# DisplayStick.net
KiCad netlist of a schematic drawn in EAGLE
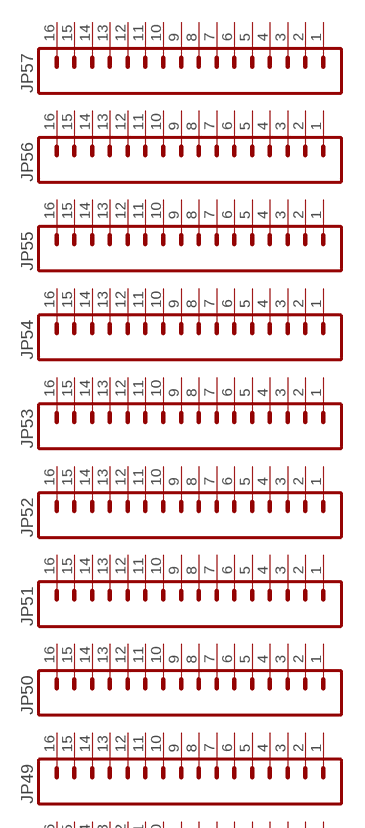
[diagram p0: schematic, sheet 1, part 1 of 2]
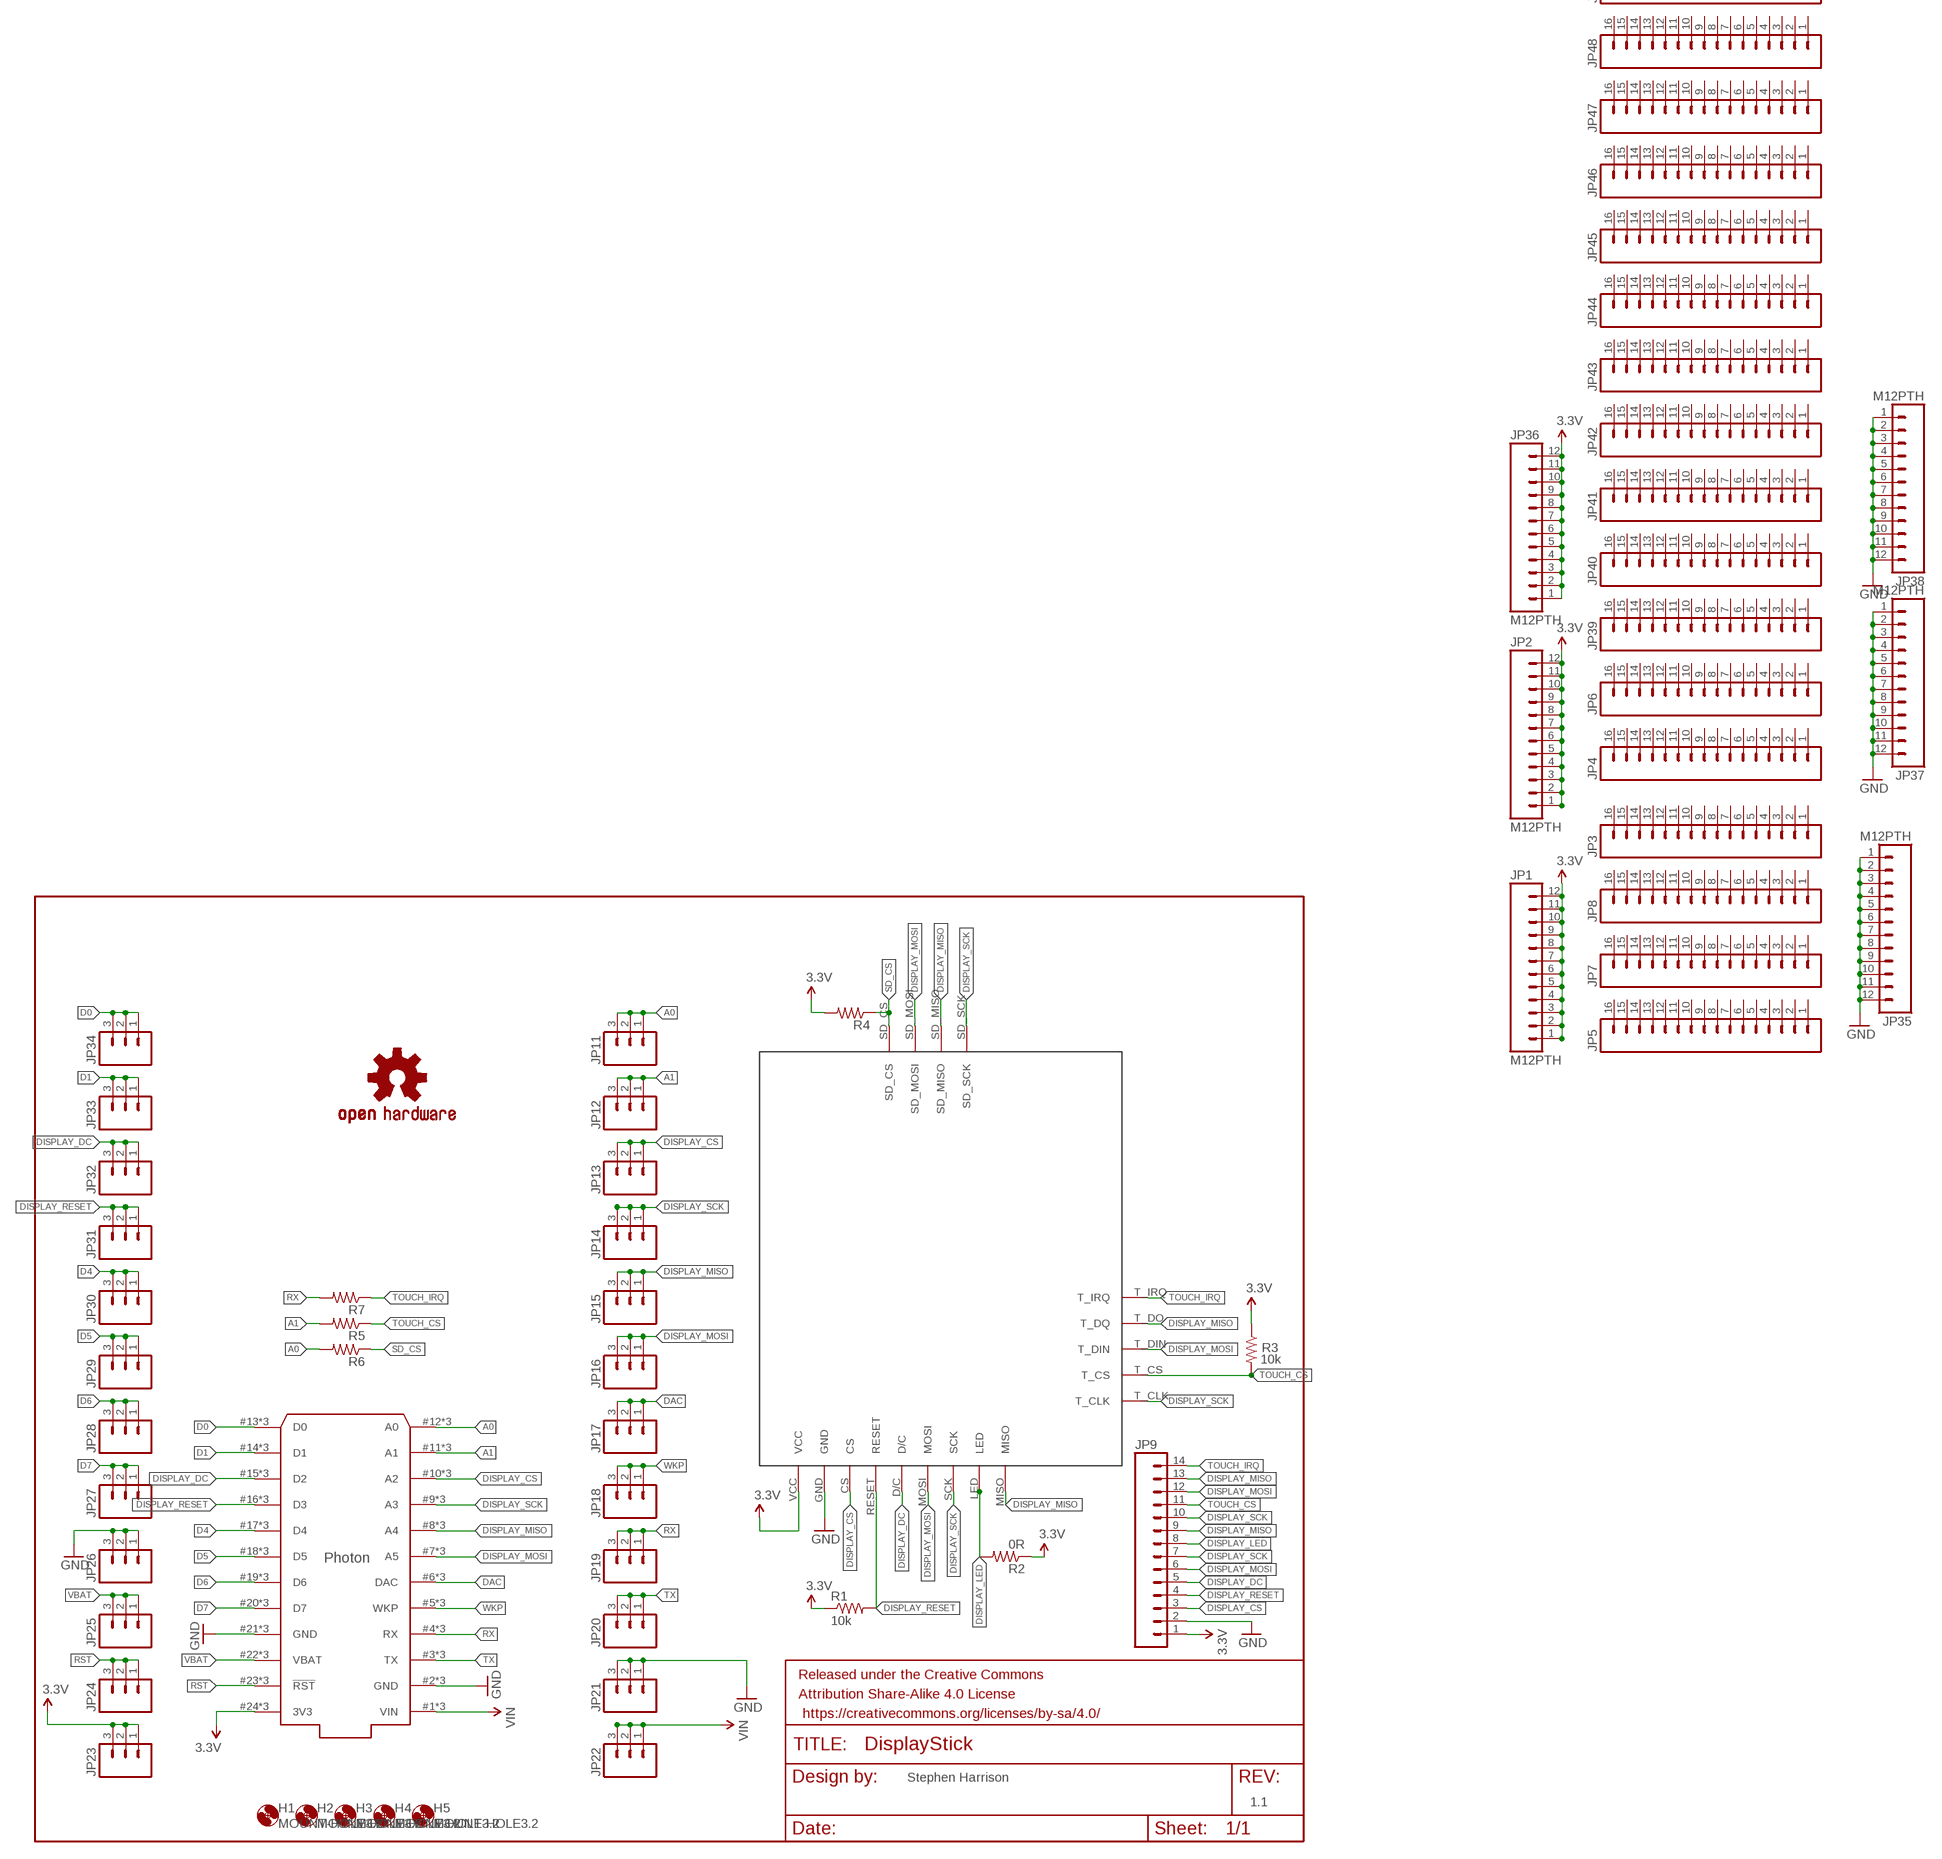
[diagram p1: schematic, sheet 1, part 2 of 2]

(export (version "E")
  (design (tool "Eeschema 10.0.6"))
  (components
    (comp (ref "FRAME1")
      (value "FRAME-LETTER")
      (footprint "eagle-import:CREATIVE_COMMONS")
      (libsource (lib "eagle-import") (part "FRAME-LETTER"))
    )
    (comp (ref "H1")
      (value "MOUNT-HOLE3.2")
      (footprint "eagle-import:3,2")
      (libsource (lib "eagle-import") (part "MOUNT-HOLE3.2"))
    )
    (comp (ref "H2")
      (value "MOUNT-HOLE3.2")
      (footprint "eagle-import:3,2")
      (libsource (lib "eagle-import") (part "MOUNT-HOLE3.2"))
    )
    (comp (ref "H3")
      (value "MOUNT-HOLE3.2")
      (footprint "eagle-import:3,2")
      (libsource (lib "eagle-import") (part "MOUNT-HOLE3.2"))
    )
    (comp (ref "H4")
      (value "MOUNT-HOLE3.2")
      (footprint "eagle-import:3,2")
      (libsource (lib "eagle-import") (part "MOUNT-HOLE3.2"))
    )
    (comp (ref "H5")
      (value "MOUNT-HOLE3.2")
      (footprint "eagle-import:3,2")
      (libsource (lib "eagle-import") (part "MOUNT-HOLE3.2"))
    )
    (comp (ref "JP1")
      (value "M12PTH")
      (footprint "eagle-import:1X12-SMALL-PADS")
      (libsource (lib "eagle-import") (part "M12PTH"))
    )
    (comp (ref "JP2")
      (value "M12PTH")
      (footprint "eagle-import:1X12-SMALL-PADS")
      (libsource (lib "eagle-import") (part "M12PTH"))
    )
    (comp (ref "JP3")
      (value "M161X16_NO_SILK")
      (footprint "eagle-import:1X16_NO_SILK")
      (libsource (lib "eagle-import") (part "M161X16_NO_SILK"))
    )
    (comp (ref "JP4")
      (value "M161X16_NO_SILK")
      (footprint "eagle-import:1X16_NO_SILK")
      (libsource (lib "eagle-import") (part "M161X16_NO_SILK"))
    )
    (comp (ref "JP5")
      (value "M161X16_NO_SILK")
      (footprint "eagle-import:1X16_NO_SILK")
      (libsource (lib "eagle-import") (part "M161X16_NO_SILK"))
    )
    (comp (ref "JP6")
      (value "M161X16_NO_SILK")
      (footprint "eagle-import:1X16_NO_SILK")
      (libsource (lib "eagle-import") (part "M161X16_NO_SILK"))
    )
    (comp (ref "JP7")
      (value "M161X16_NO_SILK")
      (footprint "eagle-import:1X16_NO_SILK")
      (libsource (lib "eagle-import") (part "M161X16_NO_SILK"))
    )
    (comp (ref "JP8")
      (value "M161X16_NO_SILK")
      (footprint "eagle-import:1X16_NO_SILK")
      (libsource (lib "eagle-import") (part "M161X16_NO_SILK"))
    )
    (comp (ref "JP9")
      (value "M14")
      (footprint "eagle-import:1X14")
      (libsource (lib "eagle-import") (part "M14"))
    )
    (comp (ref "JP11")
      (value "M03PTH")
      (footprint "eagle-import:1X03")
      (libsource (lib "eagle-import") (part "M03PTH"))
    )
    (comp (ref "JP12")
      (value "M03PTH")
      (footprint "eagle-import:1X03")
      (libsource (lib "eagle-import") (part "M03PTH"))
    )
    (comp (ref "JP13")
      (value "M03PTH")
      (footprint "eagle-import:1X03")
      (libsource (lib "eagle-import") (part "M03PTH"))
    )
    (comp (ref "JP14")
      (value "M03PTH")
      (footprint "eagle-import:1X03")
      (libsource (lib "eagle-import") (part "M03PTH"))
    )
    (comp (ref "JP15")
      (value "M03PTH")
      (footprint "eagle-import:1X03")
      (libsource (lib "eagle-import") (part "M03PTH"))
    )
    (comp (ref "JP16")
      (value "M03PTH")
      (footprint "eagle-import:1X03")
      (libsource (lib "eagle-import") (part "M03PTH"))
    )
    (comp (ref "JP17")
      (value "M03PTH")
      (footprint "eagle-import:1X03")
      (libsource (lib "eagle-import") (part "M03PTH"))
    )
    (comp (ref "JP18")
      (value "M03PTH")
      (footprint "eagle-import:1X03")
      (libsource (lib "eagle-import") (part "M03PTH"))
    )
    (comp (ref "JP19")
      (value "M03PTH")
      (footprint "eagle-import:1X03")
      (libsource (lib "eagle-import") (part "M03PTH"))
    )
    (comp (ref "JP20")
      (value "M03PTH")
      (footprint "eagle-import:1X03")
      (libsource (lib "eagle-import") (part "M03PTH"))
    )
    (comp (ref "JP21")
      (value "M03PTH")
      (footprint "eagle-import:1X03")
      (libsource (lib "eagle-import") (part "M03PTH"))
    )
    (comp (ref "JP22")
      (value "M03PTH")
      (footprint "eagle-import:1X03")
      (libsource (lib "eagle-import") (part "M03PTH"))
    )
    (comp (ref "JP23")
      (value "M03PTH")
      (footprint "eagle-import:1X03")
      (libsource (lib "eagle-import") (part "M03PTH"))
    )
    (comp (ref "JP24")
      (value "M03PTH")
      (footprint "eagle-import:1X03")
      (libsource (lib "eagle-import") (part "M03PTH"))
    )
    (comp (ref "JP25")
      (value "M03PTH")
      (footprint "eagle-import:1X03")
      (libsource (lib "eagle-import") (part "M03PTH"))
    )
    (comp (ref "JP26")
      (value "M03PTH")
      (footprint "eagle-import:1X03")
      (libsource (lib "eagle-import") (part "M03PTH"))
    )
    (comp (ref "JP27")
      (value "M03PTH")
      (footprint "eagle-import:1X03")
      (libsource (lib "eagle-import") (part "M03PTH"))
    )
    (comp (ref "JP28")
      (value "M03PTH")
      (footprint "eagle-import:1X03")
      (libsource (lib "eagle-import") (part "M03PTH"))
    )
    (comp (ref "JP29")
      (value "M03PTH")
      (footprint "eagle-import:1X03")
      (libsource (lib "eagle-import") (part "M03PTH"))
    )
    (comp (ref "JP30")
      (value "M03PTH")
      (footprint "eagle-import:1X03")
      (libsource (lib "eagle-import") (part "M03PTH"))
    )
    (comp (ref "JP31")
      (value "M03PTH")
      (footprint "eagle-import:1X03")
      (libsource (lib "eagle-import") (part "M03PTH"))
    )
    (comp (ref "JP32")
      (value "M03PTH")
      (footprint "eagle-import:1X03")
      (libsource (lib "eagle-import") (part "M03PTH"))
    )
    (comp (ref "JP33")
      (value "M03PTH")
      (footprint "eagle-import:1X03")
      (libsource (lib "eagle-import") (part "M03PTH"))
    )
    (comp (ref "JP34")
      (value "M03PTH")
      (footprint "eagle-import:1X03")
      (libsource (lib "eagle-import") (part "M03PTH"))
    )
    (comp (ref "JP35")
      (value "M12PTH")
      (footprint "eagle-import:1X12-SMALL-PADS")
      (libsource (lib "eagle-import") (part "M12PTH"))
    )
    (comp (ref "JP36")
      (value "M12PTH")
      (footprint "eagle-import:1X12-SMALL-PADS")
      (libsource (lib "eagle-import") (part "M12PTH"))
    )
    (comp (ref "JP37")
      (value "M12PTH")
      (footprint "eagle-import:1X12-SMALL-PADS")
      (libsource (lib "eagle-import") (part "M12PTH"))
    )
    (comp (ref "JP38")
      (value "M12PTH")
      (footprint "eagle-import:1X12-SMALL-PADS")
      (libsource (lib "eagle-import") (part "M12PTH"))
    )
    (comp (ref "JP39")
      (value "M161X16_NO_SILK")
      (footprint "eagle-import:1X16_NO_SILK")
      (libsource (lib "eagle-import") (part "M161X16_NO_SILK"))
    )
    (comp (ref "JP40")
      (value "M161X16_NO_SILK")
      (footprint "eagle-import:1X16_NO_SILK")
      (libsource (lib "eagle-import") (part "M161X16_NO_SILK"))
    )
    (comp (ref "JP41")
      (value "M161X16_NO_SILK")
      (footprint "eagle-import:1X16_NO_SILK")
      (libsource (lib "eagle-import") (part "M161X16_NO_SILK"))
    )
    (comp (ref "JP42")
      (value "M161X16_NO_SILK")
      (footprint "eagle-import:1X16_NO_SILK")
      (libsource (lib "eagle-import") (part "M161X16_NO_SILK"))
    )
    (comp (ref "JP43")
      (value "M161X16_NO_SILK")
      (footprint "eagle-import:1X16_NO_SILK")
      (libsource (lib "eagle-import") (part "M161X16_NO_SILK"))
    )
    (comp (ref "JP44")
      (value "M161X16_NO_SILK")
      (footprint "eagle-import:1X16_NO_SILK")
      (libsource (lib "eagle-import") (part "M161X16_NO_SILK"))
    )
    (comp (ref "JP45")
      (value "M161X16_NO_SILK")
      (footprint "eagle-import:1X16_NO_SILK")
      (libsource (lib "eagle-import") (part "M161X16_NO_SILK"))
    )
    (comp (ref "JP46")
      (value "M161X16_NO_SILK")
      (footprint "eagle-import:1X16_NO_SILK")
      (libsource (lib "eagle-import") (part "M161X16_NO_SILK"))
    )
    (comp (ref "JP47")
      (value "M161X16_NO_SILK")
      (footprint "eagle-import:1X16_NO_SILK")
      (libsource (lib "eagle-import") (part "M161X16_NO_SILK"))
    )
    (comp (ref "JP48")
      (value "M161X16_NO_SILK")
      (footprint "eagle-import:1X16_NO_SILK")
      (libsource (lib "eagle-import") (part "M161X16_NO_SILK"))
    )
    (comp (ref "JP49")
      (value "M161X16_NO_SILK")
      (footprint "eagle-import:1X16_NO_SILK")
      (libsource (lib "eagle-import") (part "M161X16_NO_SILK"))
    )
    (comp (ref "JP50")
      (value "M161X16_NO_SILK")
      (footprint "eagle-import:1X16_NO_SILK")
      (libsource (lib "eagle-import") (part "M161X16_NO_SILK"))
    )
    (comp (ref "JP51")
      (value "M161X16_NO_SILK")
      (footprint "eagle-import:1X16_NO_SILK")
      (libsource (lib "eagle-import") (part "M161X16_NO_SILK"))
    )
    (comp (ref "JP52")
      (value "M161X16_NO_SILK")
      (footprint "eagle-import:1X16_NO_SILK")
      (libsource (lib "eagle-import") (part "M161X16_NO_SILK"))
    )
    (comp (ref "JP53")
      (value "M161X16_NO_SILK")
      (footprint "eagle-import:1X16_NO_SILK")
      (libsource (lib "eagle-import") (part "M161X16_NO_SILK"))
    )
    (comp (ref "JP54")
      (value "M161X16_NO_SILK")
      (footprint "eagle-import:1X16_NO_SILK")
      (libsource (lib "eagle-import") (part "M161X16_NO_SILK"))
    )
    (comp (ref "JP55")
      (value "M161X16_NO_SILK")
      (footprint "eagle-import:1X16_NO_SILK")
      (libsource (lib "eagle-import") (part "M161X16_NO_SILK"))
    )
    (comp (ref "JP56")
      (value "M161X16_NO_SILK")
      (footprint "eagle-import:1X16_NO_SILK")
      (libsource (lib "eagle-import") (part "M161X16_NO_SILK"))
    )
    (comp (ref "JP57")
      (value "M161X16_NO_SILK")
      (footprint "eagle-import:1X16_NO_SILK")
      (libsource (lib "eagle-import") (part "M161X16_NO_SILK"))
    )
    (comp (ref "LOGO1")
      (value "OSHW-LOGOL")
      (footprint "eagle-import:OSHW-LOGO-L")
      (libsource (lib "eagle-import") (part "OSHW-LOGOL"))
    )
    (comp (ref "R1")
      (value "10k")
      (footprint "eagle-import:1206")
      (libsource (lib "eagle-import") (part "RESISTOR1206"))
    )
    (comp (ref "R2")
      (value "0R")
      (footprint "eagle-import:1206")
      (libsource (lib "eagle-import") (part "RESISTOR1206"))
    )
    (comp (ref "R3")
      (value "10k")
      (footprint "eagle-import:1206")
      (libsource (lib "eagle-import") (part "RESISTOR1206"))
    )
    (comp (ref "R4")
      (value "RESISTOR1206")
      (footprint "eagle-import:1206")
      (libsource (lib "eagle-import") (part "RESISTOR1206"))
    )
    (comp (ref "R5")
      (value "RESISTOR1206")
      (footprint "eagle-import:1206")
      (libsource (lib "eagle-import") (part "RESISTOR1206"))
    )
    (comp (ref "R6")
      (value "RESISTOR1206")
      (footprint "eagle-import:1206")
      (libsource (lib "eagle-import") (part "RESISTOR1206"))
    )
    (comp (ref "R7")
      (value "RESISTOR1206")
      (footprint "eagle-import:1206")
      (libsource (lib "eagle-import") (part "RESISTOR1206"))
    )
    (comp (ref "U$1")
      (value "TJCTM240")
      (footprint "eagle-import:TJCTM240")
      (libsource (lib "eagle-import") (part "TJCTM240"))
    )
    (comp (ref "U$3")
      (value "PHOTON_WITH_STACKABLE_HEADERS")
      (footprint "eagle-import:PHOTON_STACKABLE")
      (libsource (lib "eagle-import") (part "PHOTON_WITH_STACKABLE_HEADERS"))
    )
  )
  (nets
    (net (code "1") (name "3.3V") (class "Default")
      (node (ref "JP1") (pin "1") (pinfunction "1_1") (pintype "passive"))
      (node (ref "JP1") (pin "10") (pinfunction "10_10") (pintype "passive"))
      (node (ref "JP1") (pin "11") (pinfunction "11_11") (pintype "passive"))
      (node (ref "JP1") (pin "12") (pinfunction "12_12") (pintype "passive"))
      (node (ref "JP1") (pin "2") (pinfunction "2_2") (pintype "passive"))
      (node (ref "JP1") (pin "3") (pinfunction "3_3") (pintype "passive"))
      (node (ref "JP1") (pin "4") (pinfunction "4_4") (pintype "passive"))
      (node (ref "JP1") (pin "5") (pinfunction "5_5") (pintype "passive"))
      (node (ref "JP1") (pin "6") (pinfunction "6_6") (pintype "passive"))
      (node (ref "JP1") (pin "7") (pinfunction "7_7") (pintype "passive"))
      (node (ref "JP1") (pin "8") (pinfunction "8_8") (pintype "passive"))
      (node (ref "JP1") (pin "9") (pinfunction "9_9") (pintype "passive"))
      (node (ref "JP2") (pin "1") (pinfunction "1_1") (pintype "passive"))
      (node (ref "JP2") (pin "10") (pinfunction "10_10") (pintype "passive"))
      (node (ref "JP2") (pin "11") (pinfunction "11_11") (pintype "passive"))
      (node (ref "JP2") (pin "12") (pinfunction "12_12") (pintype "passive"))
      (node (ref "JP2") (pin "2") (pinfunction "2_2") (pintype "passive"))
      (node (ref "JP2") (pin "3") (pinfunction "3_3") (pintype "passive"))
      (node (ref "JP2") (pin "4") (pinfunction "4_4") (pintype "passive"))
      (node (ref "JP2") (pin "5") (pinfunction "5_5") (pintype "passive"))
      (node (ref "JP2") (pin "6") (pinfunction "6_6") (pintype "passive"))
      (node (ref "JP2") (pin "7") (pinfunction "7_7") (pintype "passive"))
      (node (ref "JP2") (pin "8") (pinfunction "8_8") (pintype "passive"))
      (node (ref "JP2") (pin "9") (pinfunction "9_9") (pintype "passive"))
      (node (ref "JP23") (pin "1") (pinfunction "1_1") (pintype "passive"))
      (node (ref "JP23") (pin "2") (pinfunction "2_2") (pintype "passive"))
      (node (ref "JP23") (pin "3") (pinfunction "3_3") (pintype "passive"))
      (node (ref "JP36") (pin "1") (pinfunction "1_1") (pintype "passive"))
      (node (ref "JP36") (pin "10") (pinfunction "10_10") (pintype "passive"))
      (node (ref "JP36") (pin "11") (pinfunction "11_11") (pintype "passive"))
      (node (ref "JP36") (pin "12") (pinfunction "12_12") (pintype "passive"))
      (node (ref "JP36") (pin "2") (pinfunction "2_2") (pintype "passive"))
      (node (ref "JP36") (pin "3") (pinfunction "3_3") (pintype "passive"))
      (node (ref "JP36") (pin "4") (pinfunction "4_4") (pintype "passive"))
      (node (ref "JP36") (pin "5") (pinfunction "5_5") (pintype "passive"))
      (node (ref "JP36") (pin "6") (pinfunction "6_6") (pintype "passive"))
      (node (ref "JP36") (pin "7") (pinfunction "7_7") (pintype "passive"))
      (node (ref "JP36") (pin "8") (pinfunction "8_8") (pintype "passive"))
      (node (ref "JP36") (pin "9") (pinfunction "9_9") (pintype "passive"))
      (node (ref "JP9") (pin "1") (pinfunction "1_1") (pintype "passive"))
      (node (ref "R1") (pin "1") (pinfunction "1_1") (pintype "passive"))
      (node (ref "R2") (pin "1") (pinfunction "1_1") (pintype "passive"))
      (node (ref "R3") (pin "1") (pinfunction "1_1") (pintype "passive"))
      (node (ref "R4") (pin "2") (pinfunction "2_2") (pintype "passive"))
      (node (ref "U$1") (pin "VCC") (pinfunction "VCC_VCC") (pintype "bidirectional"))
      (node (ref "U$3") (pin "#24") (pinfunction "3V3_#24") (pintype "power_in"))
      (node (ref "U$3") (pin "24") (pinfunction "3V3_24") (pintype "power_in"))
      (node (ref "U$3") (pin "@24") (pinfunction "3V3_@24") (pintype "power_in"))
    )
    (net (code "2") (name "A0") (class "Default")
      (node (ref "JP11") (pin "1") (pinfunction "1_1") (pintype "passive"))
      (node (ref "JP11") (pin "2") (pinfunction "2_2") (pintype "passive"))
      (node (ref "JP11") (pin "3") (pinfunction "3_3") (pintype "passive"))
      (node (ref "R6") (pin "2") (pinfunction "2_2") (pintype "passive"))
      (node (ref "U$3") (pin "#12") (pinfunction "A0_#12") (pintype "bidirectional"))
      (node (ref "U$3") (pin "12") (pinfunction "A0_12") (pintype "bidirectional"))
      (node (ref "U$3") (pin "@12") (pinfunction "A0_@12") (pintype "bidirectional"))
    )
    (net (code "3") (name "A1") (class "Default")
      (node (ref "JP12") (pin "1") (pinfunction "1_1") (pintype "passive"))
      (node (ref "JP12") (pin "2") (pinfunction "2_2") (pintype "passive"))
      (node (ref "JP12") (pin "3") (pinfunction "3_3") (pintype "passive"))
      (node (ref "R5") (pin "2") (pinfunction "2_2") (pintype "passive"))
      (node (ref "U$3") (pin "#11") (pinfunction "A1_#11") (pintype "bidirectional"))
      (node (ref "U$3") (pin "11") (pinfunction "A1_11") (pintype "bidirectional"))
      (node (ref "U$3") (pin "@11") (pinfunction "A1_@11") (pintype "bidirectional"))
    )
    (net (code "4") (name "D0") (class "Default")
      (node (ref "JP34") (pin "1") (pinfunction "1_1") (pintype "passive"))
      (node (ref "JP34") (pin "2") (pinfunction "2_2") (pintype "passive"))
      (node (ref "JP34") (pin "3") (pinfunction "3_3") (pintype "passive"))
      (node (ref "U$3") (pin "#13") (pinfunction "D0_#13") (pintype "bidirectional"))
      (node (ref "U$3") (pin "13") (pinfunction "D0_13") (pintype "bidirectional"))
      (node (ref "U$3") (pin "@13") (pinfunction "D0_@13") (pintype "bidirectional"))
    )
    (net (code "5") (name "D1") (class "Default")
      (node (ref "JP33") (pin "1") (pinfunction "1_1") (pintype "passive"))
      (node (ref "JP33") (pin "2") (pinfunction "2_2") (pintype "passive"))
      (node (ref "JP33") (pin "3") (pinfunction "3_3") (pintype "passive"))
      (node (ref "U$3") (pin "#14") (pinfunction "D1_#14") (pintype "bidirectional"))
      (node (ref "U$3") (pin "14") (pinfunction "D1_14") (pintype "bidirectional"))
      (node (ref "U$3") (pin "@14") (pinfunction "D1_@14") (pintype "bidirectional"))
    )
    (net (code "6") (name "D4") (class "Default")
      (node (ref "JP30") (pin "1") (pinfunction "1_1") (pintype "passive"))
      (node (ref "JP30") (pin "2") (pinfunction "2_2") (pintype "passive"))
      (node (ref "JP30") (pin "3") (pinfunction "3_3") (pintype "passive"))
      (node (ref "U$3") (pin "#17") (pinfunction "D4_#17") (pintype "bidirectional"))
      (node (ref "U$3") (pin "17") (pinfunction "D4_17") (pintype "bidirectional"))
      (node (ref "U$3") (pin "@17") (pinfunction "D4_@17") (pintype "bidirectional"))
    )
    (net (code "7") (name "D5") (class "Default")
      (node (ref "JP29") (pin "1") (pinfunction "1_1") (pintype "passive"))
      (node (ref "JP29") (pin "2") (pinfunction "2_2") (pintype "passive"))
      (node (ref "JP29") (pin "3") (pinfunction "3_3") (pintype "passive"))
      (node (ref "U$3") (pin "#18") (pinfunction "D5_#18") (pintype "bidirectional"))
      (node (ref "U$3") (pin "18") (pinfunction "D5_18") (pintype "bidirectional"))
      (node (ref "U$3") (pin "@18") (pinfunction "D5_@18") (pintype "bidirectional"))
    )
    (net (code "8") (name "D6") (class "Default")
      (node (ref "JP28") (pin "1") (pinfunction "1_1") (pintype "passive"))
      (node (ref "JP28") (pin "2") (pinfunction "2_2") (pintype "passive"))
      (node (ref "JP28") (pin "3") (pinfunction "3_3") (pintype "passive"))
      (node (ref "U$3") (pin "#19") (pinfunction "D6_#19") (pintype "bidirectional"))
      (node (ref "U$3") (pin "19") (pinfunction "D6_19") (pintype "bidirectional"))
      (node (ref "U$3") (pin "@19") (pinfunction "D6_@19") (pintype "bidirectional"))
    )
    (net (code "9") (name "D7") (class "Default")
      (node (ref "JP27") (pin "1") (pinfunction "1_1") (pintype "passive"))
      (node (ref "JP27") (pin "2") (pinfunction "2_2") (pintype "passive"))
      (node (ref "JP27") (pin "3") (pinfunction "3_3") (pintype "passive"))
      (node (ref "U$3") (pin "#20") (pinfunction "D7_#20") (pintype "bidirectional"))
      (node (ref "U$3") (pin "20") (pinfunction "D7_20") (pintype "bidirectional"))
      (node (ref "U$3") (pin "@20") (pinfunction "D7_@20") (pintype "bidirectional"))
    )
    (net (code "10") (name "DAC") (class "Default")
      (node (ref "JP17") (pin "1") (pinfunction "1_1") (pintype "passive"))
      (node (ref "JP17") (pin "2") (pinfunction "2_2") (pintype "passive"))
      (node (ref "JP17") (pin "3") (pinfunction "3_3") (pintype "passive"))
      (node (ref "U$3") (pin "#6") (pinfunction "DAC_#6") (pintype "bidirectional"))
      (node (ref "U$3") (pin "6") (pinfunction "DAC_6") (pintype "bidirectional"))
      (node (ref "U$3") (pin "@6") (pinfunction "DAC_@6") (pintype "bidirectional"))
    )
    (net (code "11") (name "DISPLAY_CS") (class "Default")
      (node (ref "JP13") (pin "1") (pinfunction "1_1") (pintype "passive"))
      (node (ref "JP13") (pin "2") (pinfunction "2_2") (pintype "passive"))
      (node (ref "JP13") (pin "3") (pinfunction "3_3") (pintype "passive"))
      (node (ref "JP9") (pin "3") (pinfunction "3_3") (pintype "passive"))
      (node (ref "U$1") (pin "CS") (pinfunction "CS_CS") (pintype "bidirectional"))
      (node (ref "U$3") (pin "#10") (pinfunction "A2_#10") (pintype "bidirectional"))
      (node (ref "U$3") (pin "10") (pinfunction "A2_10") (pintype "bidirectional"))
      (node (ref "U$3") (pin "@10") (pinfunction "A2_@10") (pintype "bidirectional"))
    )
    (net (code "12") (name "DISPLAY_DC") (class "Default")
      (node (ref "JP32") (pin "1") (pinfunction "1_1") (pintype "passive"))
      (node (ref "JP32") (pin "2") (pinfunction "2_2") (pintype "passive"))
      (node (ref "JP32") (pin "3") (pinfunction "3_3") (pintype "passive"))
      (node (ref "JP9") (pin "5") (pinfunction "5_5") (pintype "passive"))
      (node (ref "U$1") (pin "D/C") (pinfunction "D/C_D/C") (pintype "bidirectional"))
      (node (ref "U$3") (pin "#15") (pinfunction "D2_#15") (pintype "bidirectional"))
      (node (ref "U$3") (pin "15") (pinfunction "D2_15") (pintype "bidirectional"))
      (node (ref "U$3") (pin "@15") (pinfunction "D2_@15") (pintype "bidirectional"))
    )
    (net (code "13") (name "DISPLAY_LED") (class "Default")
      (node (ref "JP9") (pin "8") (pinfunction "8_8") (pintype "passive"))
      (node (ref "R2") (pin "2") (pinfunction "2_2") (pintype "passive"))
      (node (ref "U$1") (pin "LED") (pinfunction "LED_LED") (pintype "bidirectional"))
    )
    (net (code "14") (name "DISPLAY_MISO") (class "Default")
      (node (ref "JP15") (pin "1") (pinfunction "1_1") (pintype "passive"))
      (node (ref "JP15") (pin "2") (pinfunction "2_2") (pintype "passive"))
      (node (ref "JP15") (pin "3") (pinfunction "3_3") (pintype "passive"))
      (node (ref "JP9") (pin "13") (pinfunction "13_13") (pintype "passive"))
      (node (ref "JP9") (pin "9") (pinfunction "9_9") (pintype "passive"))
      (node (ref "U$1") (pin "MISO") (pinfunction "MISO_MISO") (pintype "bidirectional"))
      (node (ref "U$1") (pin "SD_MISO") (pinfunction "SD_MISO_SD_MISO") (pintype "bidirectional"))
      (node (ref "U$1") (pin "T_DO") (pinfunction "T_DQ_T_DO") (pintype "bidirectional"))
      (node (ref "U$3") (pin "#8") (pinfunction "A4_#8") (pintype "bidirectional"))
      (node (ref "U$3") (pin "8") (pinfunction "A4_8") (pintype "bidirectional"))
      (node (ref "U$3") (pin "@8") (pinfunction "A4_@8") (pintype "bidirectional"))
    )
    (net (code "15") (name "DISPLAY_MOSI") (class "Default")
      (node (ref "JP16") (pin "1") (pinfunction "1_1") (pintype "passive"))
      (node (ref "JP16") (pin "2") (pinfunction "2_2") (pintype "passive"))
      (node (ref "JP16") (pin "3") (pinfunction "3_3") (pintype "passive"))
      (node (ref "JP9") (pin "12") (pinfunction "12_12") (pintype "passive"))
      (node (ref "JP9") (pin "6") (pinfunction "6_6") (pintype "passive"))
      (node (ref "U$1") (pin "MOSI") (pinfunction "MOSI_MOSI") (pintype "bidirectional"))
      (node (ref "U$1") (pin "SD_MOSI") (pinfunction "SD_MOSI_SD_MOSI") (pintype "bidirectional"))
      (node (ref "U$1") (pin "T_DIN") (pinfunction "T_DIN_T_DIN") (pintype "bidirectional"))
      (node (ref "U$3") (pin "#7") (pinfunction "A5_#7") (pintype "bidirectional"))
      (node (ref "U$3") (pin "7") (pinfunction "A5_7") (pintype "bidirectional"))
      (node (ref "U$3") (pin "@7") (pinfunction "A5_@7") (pintype "bidirectional"))
    )
    (net (code "16") (name "DISPLAY_RESET") (class "Default")
      (node (ref "JP31") (pin "1") (pinfunction "1_1") (pintype "passive"))
      (node (ref "JP31") (pin "2") (pinfunction "2_2") (pintype "passive"))
      (node (ref "JP31") (pin "3") (pinfunction "3_3") (pintype "passive"))
      (node (ref "JP9") (pin "4") (pinfunction "4_4") (pintype "passive"))
      (node (ref "R1") (pin "2") (pinfunction "2_2") (pintype "passive"))
      (node (ref "U$1") (pin "RESET") (pinfunction "RESET_RESET") (pintype "bidirectional"))
      (node (ref "U$3") (pin "#16") (pinfunction "D3_#16") (pintype "bidirectional"))
      (node (ref "U$3") (pin "16") (pinfunction "D3_16") (pintype "bidirectional"))
      (node (ref "U$3") (pin "@16") (pinfunction "D3_@16") (pintype "bidirectional"))
    )
    (net (code "17") (name "DISPLAY_SCK") (class "Default")
      (node (ref "JP14") (pin "1") (pinfunction "1_1") (pintype "passive"))
      (node (ref "JP14") (pin "2") (pinfunction "2_2") (pintype "passive"))
      (node (ref "JP14") (pin "3") (pinfunction "3_3") (pintype "passive"))
      (node (ref "JP9") (pin "10") (pinfunction "10_10") (pintype "passive"))
      (node (ref "JP9") (pin "7") (pinfunction "7_7") (pintype "passive"))
      (node (ref "U$1") (pin "SCK") (pinfunction "SCK_SCK") (pintype "bidirectional"))
      (node (ref "U$1") (pin "SD_SCK") (pinfunction "SD_SCK_SD_SCK") (pintype "bidirectional"))
      (node (ref "U$1") (pin "T_CLK") (pinfunction "T_CLK_T_CLK") (pintype "bidirectional"))
      (node (ref "U$3") (pin "#9") (pinfunction "A3_#9") (pintype "bidirectional"))
      (node (ref "U$3") (pin "9") (pinfunction "A3_9") (pintype "bidirectional"))
      (node (ref "U$3") (pin "@9") (pinfunction "A3_@9") (pintype "bidirectional"))
    )
    (net (code "18") (name "GND") (class "Default")
      (node (ref "JP21") (pin "1") (pinfunction "1_1") (pintype "passive"))
      (node (ref "JP21") (pin "2") (pinfunction "2_2") (pintype "passive"))
      (node (ref "JP21") (pin "3") (pinfunction "3_3") (pintype "passive"))
      (node (ref "JP26") (pin "1") (pinfunction "1_1") (pintype "passive"))
      (node (ref "JP26") (pin "2") (pinfunction "2_2") (pintype "passive"))
      (node (ref "JP26") (pin "3") (pinfunction "3_3") (pintype "passive"))
      (node (ref "JP35") (pin "1") (pinfunction "1_1") (pintype "passive"))
      (node (ref "JP35") (pin "10") (pinfunction "10_10") (pintype "passive"))
      (node (ref "JP35") (pin "11") (pinfunction "11_11") (pintype "passive"))
      (node (ref "JP35") (pin "12") (pinfunction "12_12") (pintype "passive"))
      (node (ref "JP35") (pin "2") (pinfunction "2_2") (pintype "passive"))
      (node (ref "JP35") (pin "3") (pinfunction "3_3") (pintype "passive"))
      (node (ref "JP35") (pin "4") (pinfunction "4_4") (pintype "passive"))
      (node (ref "JP35") (pin "5") (pinfunction "5_5") (pintype "passive"))
      (node (ref "JP35") (pin "6") (pinfunction "6_6") (pintype "passive"))
      (node (ref "JP35") (pin "7") (pinfunction "7_7") (pintype "passive"))
      (node (ref "JP35") (pin "8") (pinfunction "8_8") (pintype "passive"))
      (node (ref "JP35") (pin "9") (pinfunction "9_9") (pintype "passive"))
      (node (ref "JP37") (pin "1") (pinfunction "1_1") (pintype "passive"))
      (node (ref "JP37") (pin "10") (pinfunction "10_10") (pintype "passive"))
      (node (ref "JP37") (pin "11") (pinfunction "11_11") (pintype "passive"))
      (node (ref "JP37") (pin "12") (pinfunction "12_12") (pintype "passive"))
      (node (ref "JP37") (pin "2") (pinfunction "2_2") (pintype "passive"))
      (node (ref "JP37") (pin "3") (pinfunction "3_3") (pintype "passive"))
      (node (ref "JP37") (pin "4") (pinfunction "4_4") (pintype "passive"))
      (node (ref "JP37") (pin "5") (pinfunction "5_5") (pintype "passive"))
      (node (ref "JP37") (pin "6") (pinfunction "6_6") (pintype "passive"))
      (node (ref "JP37") (pin "7") (pinfunction "7_7") (pintype "passive"))
      (node (ref "JP37") (pin "8") (pinfunction "8_8") (pintype "passive"))
      (node (ref "JP37") (pin "9") (pinfunction "9_9") (pintype "passive"))
      (node (ref "JP38") (pin "1") (pinfunction "1_1") (pintype "passive"))
      (node (ref "JP38") (pin "10") (pinfunction "10_10") (pintype "passive"))
      (node (ref "JP38") (pin "11") (pinfunction "11_11") (pintype "passive"))
      (node (ref "JP38") (pin "12") (pinfunction "12_12") (pintype "passive"))
      (node (ref "JP38") (pin "2") (pinfunction "2_2") (pintype "passive"))
      (node (ref "JP38") (pin "3") (pinfunction "3_3") (pintype "passive"))
      (node (ref "JP38") (pin "4") (pinfunction "4_4") (pintype "passive"))
      (node (ref "JP38") (pin "5") (pinfunction "5_5") (pintype "passive"))
      (node (ref "JP38") (pin "6") (pinfunction "6_6") (pintype "passive"))
      (node (ref "JP38") (pin "7") (pinfunction "7_7") (pintype "passive"))
      (node (ref "JP38") (pin "8") (pinfunction "8_8") (pintype "passive"))
      (node (ref "JP38") (pin "9") (pinfunction "9_9") (pintype "passive"))
      (node (ref "JP9") (pin "2") (pinfunction "2_2") (pintype "passive"))
      (node (ref "U$1") (pin "GND") (pinfunction "GND_GND") (pintype "bidirectional"))
      (node (ref "U$3") (pin "#2") (pinfunction "GND_#2") (pintype "power_in"))
      (node (ref "U$3") (pin "#21") (pinfunction "GND_#21") (pintype "power_in"))
      (node (ref "U$3") (pin "2") (pinfunction "GND_2") (pintype "power_in"))
      (node (ref "U$3") (pin "21") (pinfunction "GND_21") (pintype "power_in"))
      (node (ref "U$3") (pin "@2") (pinfunction "GND_@2") (pintype "power_in"))
      (node (ref "U$3") (pin "@21") (pinfunction "GND_@21") (pintype "power_in"))
    )
    (net (code "19") (name "RST") (class "Default")
      (node (ref "JP24") (pin "1") (pinfunction "1_1") (pintype "passive"))
      (node (ref "JP24") (pin "2") (pinfunction "2_2") (pintype "passive"))
      (node (ref "JP24") (pin "3") (pinfunction "3_3") (pintype "passive"))
      (node (ref "U$3") (pin "#23") (pinfunction "~{RST}_#23") (pintype "bidirectional"))
      (node (ref "U$3") (pin "23") (pinfunction "~{RST}_23") (pintype "bidirectional"))
      (node (ref "U$3") (pin "@23") (pinfunction "~{RST}_@23") (pintype "bidirectional"))
    )
    (net (code "20") (name "RX") (class "Default")
      (node (ref "JP19") (pin "1") (pinfunction "1_1") (pintype "passive"))
      (node (ref "JP19") (pin "2") (pinfunction "2_2") (pintype "passive"))
      (node (ref "JP19") (pin "3") (pinfunction "3_3") (pintype "passive"))
      (node (ref "R7") (pin "2") (pinfunction "2_2") (pintype "passive"))
      (node (ref "U$3") (pin "#4") (pinfunction "RX_#4") (pintype "bidirectional"))
      (node (ref "U$3") (pin "4") (pinfunction "RX_4") (pintype "bidirectional"))
      (node (ref "U$3") (pin "@4") (pinfunction "RX_@4") (pintype "bidirectional"))
    )
    (net (code "21") (name "SD_CS") (class "Default")
      (node (ref "R4") (pin "1") (pinfunction "1_1") (pintype "passive"))
      (node (ref "R6") (pin "1") (pinfunction "1_1") (pintype "passive"))
      (node (ref "U$1") (pin "SD_CS") (pinfunction "SD_CS_SD_CS") (pintype "bidirectional"))
    )
    (net (code "22") (name "TOUCH_CS") (class "Default")
      (node (ref "JP9") (pin "11") (pinfunction "11_11") (pintype "passive"))
      (node (ref "R3") (pin "2") (pinfunction "2_2") (pintype "passive"))
      (node (ref "R5") (pin "1") (pinfunction "1_1") (pintype "passive"))
      (node (ref "U$1") (pin "T_CS") (pinfunction "T_CS_T_CS") (pintype "bidirectional"))
    )
    (net (code "23") (name "TOUCH_IRQ") (class "Default")
      (node (ref "JP9") (pin "14") (pinfunction "14_14") (pintype "passive"))
      (node (ref "R7") (pin "1") (pinfunction "1_1") (pintype "passive"))
      (node (ref "U$1") (pin "T_IRQ") (pinfunction "T_IRQ_T_IRQ") (pintype "bidirectional"))
    )
    (net (code "24") (name "TX") (class "Default")
      (node (ref "JP20") (pin "1") (pinfunction "1_1") (pintype "passive"))
      (node (ref "JP20") (pin "2") (pinfunction "2_2") (pintype "passive"))
      (node (ref "JP20") (pin "3") (pinfunction "3_3") (pintype "passive"))
      (node (ref "U$3") (pin "#3") (pinfunction "TX_#3") (pintype "bidirectional"))
      (node (ref "U$3") (pin "3") (pinfunction "TX_3") (pintype "bidirectional"))
      (node (ref "U$3") (pin "@3") (pinfunction "TX_@3") (pintype "bidirectional"))
    )
    (net (code "25") (name "VBAT") (class "Default")
      (node (ref "JP25") (pin "1") (pinfunction "1_1") (pintype "passive"))
      (node (ref "JP25") (pin "2") (pinfunction "2_2") (pintype "passive"))
      (node (ref "JP25") (pin "3") (pinfunction "3_3") (pintype "passive"))
      (node (ref "U$3") (pin "#22") (pinfunction "VBAT_#22") (pintype "power_in"))
      (node (ref "U$3") (pin "22") (pinfunction "VBAT_22") (pintype "power_in"))
      (node (ref "U$3") (pin "@22") (pinfunction "VBAT_@22") (pintype "power_in"))
    )
    (net (code "26") (name "VIN") (class "Default")
      (node (ref "JP22") (pin "1") (pinfunction "1_1") (pintype "passive"))
      (node (ref "JP22") (pin "2") (pinfunction "2_2") (pintype "passive"))
      (node (ref "JP22") (pin "3") (pinfunction "3_3") (pintype "passive"))
      (node (ref "U$3") (pin "#1") (pinfunction "VIN_#1") (pintype "power_in"))
      (node (ref "U$3") (pin "1") (pinfunction "VIN_1") (pintype "power_in"))
      (node (ref "U$3") (pin "@1") (pinfunction "VIN_@1") (pintype "power_in"))
    )
    (net (code "27") (name "WKP") (class "Default")
      (node (ref "JP18") (pin "1") (pinfunction "1_1") (pintype "passive"))
      (node (ref "JP18") (pin "2") (pinfunction "2_2") (pintype "passive"))
      (node (ref "JP18") (pin "3") (pinfunction "3_3") (pintype "passive"))
      (node (ref "U$3") (pin "#5") (pinfunction "WKP_#5") (pintype "bidirectional"))
      (node (ref "U$3") (pin "5") (pinfunction "WKP_5") (pintype "bidirectional"))
      (node (ref "U$3") (pin "@5") (pinfunction "WKP_@5") (pintype "bidirectional"))
    )
    (net (code "28") (name "unconnected-(JP3-Pad1)") (class "Default")
      (node (ref "JP3") (pin "1") (pinfunction "1_1") (pintype "passive"))
    )
    (net (code "29") (name "unconnected-(JP3-Pad2)") (class "Default")
      (node (ref "JP3") (pin "2") (pinfunction "2_2") (pintype "passive"))
    )
    (net (code "30") (name "unconnected-(JP3-Pad3)") (class "Default")
      (node (ref "JP3") (pin "3") (pinfunction "3_3") (pintype "passive"))
    )
    (net (code "31") (name "unconnected-(JP3-Pad4)") (class "Default")
      (node (ref "JP3") (pin "4") (pinfunction "4_4") (pintype "passive"))
    )
    (net (code "32") (name "unconnected-(JP3-Pad5)") (class "Default")
      (node (ref "JP3") (pin "5") (pinfunction "5_5") (pintype "passive"))
    )
    (net (code "33") (name "unconnected-(JP3-Pad6)") (class "Default")
      (node (ref "JP3") (pin "6") (pinfunction "6_6") (pintype "passive"))
    )
    (net (code "34") (name "unconnected-(JP3-Pad7)") (class "Default")
      (node (ref "JP3") (pin "7") (pinfunction "7_7") (pintype "passive"))
    )
    (net (code "35") (name "unconnected-(JP3-Pad8)") (class "Default")
      (node (ref "JP3") (pin "8") (pinfunction "8_8") (pintype "passive"))
    )
    (net (code "36") (name "unconnected-(JP3-Pad9)") (class "Default")
      (node (ref "JP3") (pin "9") (pinfunction "9_9") (pintype "passive"))
    )
    (net (code "37") (name "unconnected-(JP3-Pad10)") (class "Default")
      (node (ref "JP3") (pin "10") (pinfunction "10_10") (pintype "passive"))
    )
    (net (code "38") (name "unconnected-(JP3-Pad11)") (class "Default")
      (node (ref "JP3") (pin "11") (pinfunction "11_11") (pintype "passive"))
    )
    (net (code "39") (name "unconnected-(JP3-Pad12)") (class "Default")
      (node (ref "JP3") (pin "12") (pinfunction "12_12") (pintype "passive"))
    )
    (net (code "40") (name "unconnected-(JP3-Pad13)") (class "Default")
      (node (ref "JP3") (pin "13") (pinfunction "13_13") (pintype "passive"))
    )
    (net (code "41") (name "unconnected-(JP3-Pad14)") (class "Default")
      (node (ref "JP3") (pin "14") (pinfunction "14_14") (pintype "passive"))
    )
    (net (code "42") (name "unconnected-(JP3-Pad15)") (class "Default")
      (node (ref "JP3") (pin "15") (pinfunction "15_15") (pintype "passive"))
    )
    (net (code "43") (name "unconnected-(JP3-Pad16)") (class "Default")
      (node (ref "JP3") (pin "16") (pinfunction "16_16") (pintype "passive"))
    )
    (net (code "44") (name "unconnected-(JP4-Pad1)") (class "Default")
      (node (ref "JP4") (pin "1") (pinfunction "1_1") (pintype "passive"))
    )
    (net (code "45") (name "unconnected-(JP4-Pad2)") (class "Default")
      (node (ref "JP4") (pin "2") (pinfunction "2_2") (pintype "passive"))
    )
    (net (code "46") (name "unconnected-(JP4-Pad3)") (class "Default")
      (node (ref "JP4") (pin "3") (pinfunction "3_3") (pintype "passive"))
    )
    (net (code "47") (name "unconnected-(JP4-Pad4)") (class "Default")
      (node (ref "JP4") (pin "4") (pinfunction "4_4") (pintype "passive"))
    )
    (net (code "48") (name "unconnected-(JP4-Pad5)") (class "Default")
      (node (ref "JP4") (pin "5") (pinfunction "5_5") (pintype "passive"))
    )
    (net (code "49") (name "unconnected-(JP4-Pad6)") (class "Default")
      (node (ref "JP4") (pin "6") (pinfunction "6_6") (pintype "passive"))
    )
    (net (code "50") (name "unconnected-(JP4-Pad7)") (class "Default")
      (node (ref "JP4") (pin "7") (pinfunction "7_7") (pintype "passive"))
    )
    (net (code "51") (name "unconnected-(JP4-Pad8)") (class "Default")
      (node (ref "JP4") (pin "8") (pinfunction "8_8") (pintype "passive"))
    )
    (net (code "52") (name "unconnected-(JP4-Pad9)") (class "Default")
      (node (ref "JP4") (pin "9") (pinfunction "9_9") (pintype "passive"))
    )
    (net (code "53") (name "unconnected-(JP4-Pad10)") (class "Default")
      (node (ref "JP4") (pin "10") (pinfunction "10_10") (pintype "passive"))
    )
    (net (code "54") (name "unconnected-(JP4-Pad11)") (class "Default")
      (node (ref "JP4") (pin "11") (pinfunction "11_11") (pintype "passive"))
    )
    (net (code "55") (name "unconnected-(JP4-Pad12)") (class "Default")
      (node (ref "JP4") (pin "12") (pinfunction "12_12") (pintype "passive"))
    )
    (net (code "56") (name "unconnected-(JP4-Pad13)") (class "Default")
      (node (ref "JP4") (pin "13") (pinfunction "13_13") (pintype "passive"))
    )
    (net (code "57") (name "unconnected-(JP4-Pad14)") (class "Default")
      (node (ref "JP4") (pin "14") (pinfunction "14_14") (pintype "passive"))
    )
    (net (code "58") (name "unconnected-(JP4-Pad15)") (class "Default")
      (node (ref "JP4") (pin "15") (pinfunction "15_15") (pintype "passive"))
    )
    (net (code "59") (name "unconnected-(JP4-Pad16)") (class "Default")
      (node (ref "JP4") (pin "16") (pinfunction "16_16") (pintype "passive"))
    )
    (net (code "60") (name "unconnected-(JP5-Pad1)") (class "Default")
      (node (ref "JP5") (pin "1") (pinfunction "1_1") (pintype "passive"))
    )
    (net (code "61") (name "unconnected-(JP5-Pad2)") (class "Default")
      (node (ref "JP5") (pin "2") (pinfunction "2_2") (pintype "passive"))
    )
    (net (code "62") (name "unconnected-(JP5-Pad3)") (class "Default")
      (node (ref "JP5") (pin "3") (pinfunction "3_3") (pintype "passive"))
    )
    (net (code "63") (name "unconnected-(JP5-Pad4)") (class "Default")
      (node (ref "JP5") (pin "4") (pinfunction "4_4") (pintype "passive"))
    )
    (net (code "64") (name "unconnected-(JP5-Pad5)") (class "Default")
      (node (ref "JP5") (pin "5") (pinfunction "5_5") (pintype "passive"))
    )
    (net (code "65") (name "unconnected-(JP5-Pad6)") (class "Default")
      (node (ref "JP5") (pin "6") (pinfunction "6_6") (pintype "passive"))
    )
    (net (code "66") (name "unconnected-(JP5-Pad7)") (class "Default")
      (node (ref "JP5") (pin "7") (pinfunction "7_7") (pintype "passive"))
    )
    (net (code "67") (name "unconnected-(JP5-Pad8)") (class "Default")
      (node (ref "JP5") (pin "8") (pinfunction "8_8") (pintype "passive"))
    )
    (net (code "68") (name "unconnected-(JP5-Pad9)") (class "Default")
      (node (ref "JP5") (pin "9") (pinfunction "9_9") (pintype "passive"))
    )
    (net (code "69") (name "unconnected-(JP5-Pad10)") (class "Default")
      (node (ref "JP5") (pin "10") (pinfunction "10_10") (pintype "passive"))
    )
    (net (code "70") (name "unconnected-(JP5-Pad11)") (class "Default")
      (node (ref "JP5") (pin "11") (pinfunction "11_11") (pintype "passive"))
    )
    (net (code "71") (name "unconnected-(JP5-Pad12)") (class "Default")
      (node (ref "JP5") (pin "12") (pinfunction "12_12") (pintype "passive"))
    )
    (net (code "72") (name "unconnected-(JP5-Pad13)") (class "Default")
      (node (ref "JP5") (pin "13") (pinfunction "13_13") (pintype "passive"))
    )
    (net (code "73") (name "unconnected-(JP5-Pad14)") (class "Default")
      (node (ref "JP5") (pin "14") (pinfunction "14_14") (pintype "passive"))
    )
    (net (code "74") (name "unconnected-(JP5-Pad15)") (class "Default")
      (node (ref "JP5") (pin "15") (pinfunction "15_15") (pintype "passive"))
    )
    (net (code "75") (name "unconnected-(JP5-Pad16)") (class "Default")
      (node (ref "JP5") (pin "16") (pinfunction "16_16") (pintype "passive"))
    )
    (net (code "76") (name "unconnected-(JP6-Pad1)") (class "Default")
      (node (ref "JP6") (pin "1") (pinfunction "1_1") (pintype "passive"))
    )
    (net (code "77") (name "unconnected-(JP6-Pad2)") (class "Default")
      (node (ref "JP6") (pin "2") (pinfunction "2_2") (pintype "passive"))
    )
    (net (code "78") (name "unconnected-(JP6-Pad3)") (class "Default")
      (node (ref "JP6") (pin "3") (pinfunction "3_3") (pintype "passive"))
    )
    (net (code "79") (name "unconnected-(JP6-Pad4)") (class "Default")
      (node (ref "JP6") (pin "4") (pinfunction "4_4") (pintype "passive"))
    )
    (net (code "80") (name "unconnected-(JP6-Pad5)") (class "Default")
      (node (ref "JP6") (pin "5") (pinfunction "5_5") (pintype "passive"))
    )
    (net (code "81") (name "unconnected-(JP6-Pad6)") (class "Default")
      (node (ref "JP6") (pin "6") (pinfunction "6_6") (pintype "passive"))
    )
    (net (code "82") (name "unconnected-(JP6-Pad7)") (class "Default")
      (node (ref "JP6") (pin "7") (pinfunction "7_7") (pintype "passive"))
    )
    (net (code "83") (name "unconnected-(JP6-Pad8)") (class "Default")
      (node (ref "JP6") (pin "8") (pinfunction "8_8") (pintype "passive"))
    )
    (net (code "84") (name "unconnected-(JP6-Pad9)") (class "Default")
      (node (ref "JP6") (pin "9") (pinfunction "9_9") (pintype "passive"))
    )
    (net (code "85") (name "unconnected-(JP6-Pad10)") (class "Default")
      (node (ref "JP6") (pin "10") (pinfunction "10_10") (pintype "passive"))
    )
    (net (code "86") (name "unconnected-(JP6-Pad11)") (class "Default")
      (node (ref "JP6") (pin "11") (pinfunction "11_11") (pintype "passive"))
    )
    (net (code "87") (name "unconnected-(JP6-Pad12)") (class "Default")
      (node (ref "JP6") (pin "12") (pinfunction "12_12") (pintype "passive"))
    )
    (net (code "88") (name "unconnected-(JP6-Pad13)") (class "Default")
      (node (ref "JP6") (pin "13") (pinfunction "13_13") (pintype "passive"))
    )
    (net (code "89") (name "unconnected-(JP6-Pad14)") (class "Default")
      (node (ref "JP6") (pin "14") (pinfunction "14_14") (pintype "passive"))
    )
    (net (code "90") (name "unconnected-(JP6-Pad15)") (class "Default")
      (node (ref "JP6") (pin "15") (pinfunction "15_15") (pintype "passive"))
    )
    (net (code "91") (name "unconnected-(JP6-Pad16)") (class "Default")
      (node (ref "JP6") (pin "16") (pinfunction "16_16") (pintype "passive"))
    )
    (net (code "92") (name "unconnected-(JP7-Pad1)") (class "Default")
      (node (ref "JP7") (pin "1") (pinfunction "1_1") (pintype "passive"))
    )
    (net (code "93") (name "unconnected-(JP7-Pad2)") (class "Default")
      (node (ref "JP7") (pin "2") (pinfunction "2_2") (pintype "passive"))
    )
    (net (code "94") (name "unconnected-(JP7-Pad3)") (class "Default")
      (node (ref "JP7") (pin "3") (pinfunction "3_3") (pintype "passive"))
    )
    (net (code "95") (name "unconnected-(JP7-Pad4)") (class "Default")
      (node (ref "JP7") (pin "4") (pinfunction "4_4") (pintype "passive"))
    )
    (net (code "96") (name "unconnected-(JP7-Pad5)") (class "Default")
      (node (ref "JP7") (pin "5") (pinfunction "5_5") (pintype "passive"))
    )
    (net (code "97") (name "unconnected-(JP7-Pad6)") (class "Default")
      (node (ref "JP7") (pin "6") (pinfunction "6_6") (pintype "passive"))
    )
    (net (code "98") (name "unconnected-(JP7-Pad7)") (class "Default")
      (node (ref "JP7") (pin "7") (pinfunction "7_7") (pintype "passive"))
    )
    (net (code "99") (name "unconnected-(JP7-Pad8)") (class "Default")
      (node (ref "JP7") (pin "8") (pinfunction "8_8") (pintype "passive"))
    )
    (net (code "100") (name "unconnected-(JP7-Pad9)") (class "Default")
      (node (ref "JP7") (pin "9") (pinfunction "9_9") (pintype "passive"))
    )
    (net (code "101") (name "unconnected-(JP7-Pad10)") (class "Default")
      (node (ref "JP7") (pin "10") (pinfunction "10_10") (pintype "passive"))
    )
    (net (code "102") (name "unconnected-(JP7-Pad11)") (class "Default")
      (node (ref "JP7") (pin "11") (pinfunction "11_11") (pintype "passive"))
    )
    (net (code "103") (name "unconnected-(JP7-Pad12)") (class "Default")
      (node (ref "JP7") (pin "12") (pinfunction "12_12") (pintype "passive"))
    )
    (net (code "104") (name "unconnected-(JP7-Pad13)") (class "Default")
      (node (ref "JP7") (pin "13") (pinfunction "13_13") (pintype "passive"))
    )
    (net (code "105") (name "unconnected-(JP7-Pad14)") (class "Default")
      (node (ref "JP7") (pin "14") (pinfunction "14_14") (pintype "passive"))
    )
    (net (code "106") (name "unconnected-(JP7-Pad15)") (class "Default")
      (node (ref "JP7") (pin "15") (pinfunction "15_15") (pintype "passive"))
    )
    (net (code "107") (name "unconnected-(JP7-Pad16)") (class "Default")
      (node (ref "JP7") (pin "16") (pinfunction "16_16") (pintype "passive"))
    )
    (net (code "108") (name "unconnected-(JP8-Pad1)") (class "Default")
      (node (ref "JP8") (pin "1") (pinfunction "1_1") (pintype "passive"))
    )
    (net (code "109") (name "unconnected-(JP8-Pad2)") (class "Default")
      (node (ref "JP8") (pin "2") (pinfunction "2_2") (pintype "passive"))
    )
    (net (code "110") (name "unconnected-(JP8-Pad3)") (class "Default")
      (node (ref "JP8") (pin "3") (pinfunction "3_3") (pintype "passive"))
    )
    (net (code "111") (name "unconnected-(JP8-Pad4)") (class "Default")
      (node (ref "JP8") (pin "4") (pinfunction "4_4") (pintype "passive"))
    )
    (net (code "112") (name "unconnected-(JP8-Pad5)") (class "Default")
      (node (ref "JP8") (pin "5") (pinfunction "5_5") (pintype "passive"))
    )
    (net (code "113") (name "unconnected-(JP8-Pad6)") (class "Default")
      (node (ref "JP8") (pin "6") (pinfunction "6_6") (pintype "passive"))
    )
    (net (code "114") (name "unconnected-(JP8-Pad7)") (class "Default")
      (node (ref "JP8") (pin "7") (pinfunction "7_7") (pintype "passive"))
    )
    (net (code "115") (name "unconnected-(JP8-Pad8)") (class "Default")
      (node (ref "JP8") (pin "8") (pinfunction "8_8") (pintype "passive"))
    )
    (net (code "116") (name "unconnected-(JP8-Pad9)") (class "Default")
      (node (ref "JP8") (pin "9") (pinfunction "9_9") (pintype "passive"))
    )
    (net (code "117") (name "unconnected-(JP8-Pad10)") (class "Default")
      (node (ref "JP8") (pin "10") (pinfunction "10_10") (pintype "passive"))
    )
    (net (code "118") (name "unconnected-(JP8-Pad11)") (class "Default")
      (node (ref "JP8") (pin "11") (pinfunction "11_11") (pintype "passive"))
    )
    (net (code "119") (name "unconnected-(JP8-Pad12)") (class "Default")
      (node (ref "JP8") (pin "12") (pinfunction "12_12") (pintype "passive"))
    )
    (net (code "120") (name "unconnected-(JP8-Pad13)") (class "Default")
      (node (ref "JP8") (pin "13") (pinfunction "13_13") (pintype "passive"))
    )
    (net (code "121") (name "unconnected-(JP8-Pad14)") (class "Default")
      (node (ref "JP8") (pin "14") (pinfunction "14_14") (pintype "passive"))
    )
    (net (code "122") (name "unconnected-(JP8-Pad15)") (class "Default")
      (node (ref "JP8") (pin "15") (pinfunction "15_15") (pintype "passive"))
    )
    (net (code "123") (name "unconnected-(JP8-Pad16)") (class "Default")
      (node (ref "JP8") (pin "16") (pinfunction "16_16") (pintype "passive"))
    )
    (net (code "124") (name "unconnected-(JP39-Pad1)") (class "Default")
      (node (ref "JP39") (pin "1") (pinfunction "1_1") (pintype "passive"))
    )
    (net (code "125") (name "unconnected-(JP39-Pad2)") (class "Default")
      (node (ref "JP39") (pin "2") (pinfunction "2_2") (pintype "passive"))
    )
    (net (code "126") (name "unconnected-(JP39-Pad3)") (class "Default")
      (node (ref "JP39") (pin "3") (pinfunction "3_3") (pintype "passive"))
    )
    (net (code "127") (name "unconnected-(JP39-Pad4)") (class "Default")
      (node (ref "JP39") (pin "4") (pinfunction "4_4") (pintype "passive"))
    )
    (net (code "128") (name "unconnected-(JP39-Pad5)") (class "Default")
      (node (ref "JP39") (pin "5") (pinfunction "5_5") (pintype "passive"))
    )
    (net (code "129") (name "unconnected-(JP39-Pad6)") (class "Default")
      (node (ref "JP39") (pin "6") (pinfunction "6_6") (pintype "passive"))
    )
    (net (code "130") (name "unconnected-(JP39-Pad7)") (class "Default")
      (node (ref "JP39") (pin "7") (pinfunction "7_7") (pintype "passive"))
    )
    (net (code "131") (name "unconnected-(JP39-Pad8)") (class "Default")
      (node (ref "JP39") (pin "8") (pinfunction "8_8") (pintype "passive"))
    )
    (net (code "132") (name "unconnected-(JP39-Pad9)") (class "Default")
      (node (ref "JP39") (pin "9") (pinfunction "9_9") (pintype "passive"))
    )
    (net (code "133") (name "unconnected-(JP39-Pad10)") (class "Default")
      (node (ref "JP39") (pin "10") (pinfunction "10_10") (pintype "passive"))
    )
    (net (code "134") (name "unconnected-(JP39-Pad11)") (class "Default")
      (node (ref "JP39") (pin "11") (pinfunction "11_11") (pintype "passive"))
    )
    (net (code "135") (name "unconnected-(JP39-Pad12)") (class "Default")
      (node (ref "JP39") (pin "12") (pinfunction "12_12") (pintype "passive"))
    )
    (net (code "136") (name "unconnected-(JP39-Pad13)") (class "Default")
      (node (ref "JP39") (pin "13") (pinfunction "13_13") (pintype "passive"))
    )
    (net (code "137") (name "unconnected-(JP39-Pad14)") (class "Default")
      (node (ref "JP39") (pin "14") (pinfunction "14_14") (pintype "passive"))
    )
    (net (code "138") (name "unconnected-(JP39-Pad15)") (class "Default")
      (node (ref "JP39") (pin "15") (pinfunction "15_15") (pintype "passive"))
    )
    (net (code "139") (name "unconnected-(JP39-Pad16)") (class "Default")
      (node (ref "JP39") (pin "16") (pinfunction "16_16") (pintype "passive"))
    )
    (net (code "140") (name "unconnected-(JP40-Pad1)") (class "Default")
      (node (ref "JP40") (pin "1") (pinfunction "1_1") (pintype "passive"))
    )
    (net (code "141") (name "unconnected-(JP40-Pad2)") (class "Default")
      (node (ref "JP40") (pin "2") (pinfunction "2_2") (pintype "passive"))
    )
    (net (code "142") (name "unconnected-(JP40-Pad3)") (class "Default")
      (node (ref "JP40") (pin "3") (pinfunction "3_3") (pintype "passive"))
    )
    (net (code "143") (name "unconnected-(JP40-Pad4)") (class "Default")
      (node (ref "JP40") (pin "4") (pinfunction "4_4") (pintype "passive"))
    )
    (net (code "144") (name "unconnected-(JP40-Pad5)") (class "Default")
      (node (ref "JP40") (pin "5") (pinfunction "5_5") (pintype "passive"))
    )
    (net (code "145") (name "unconnected-(JP40-Pad6)") (class "Default")
      (node (ref "JP40") (pin "6") (pinfunction "6_6") (pintype "passive"))
    )
    (net (code "146") (name "unconnected-(JP40-Pad7)") (class "Default")
      (node (ref "JP40") (pin "7") (pinfunction "7_7") (pintype "passive"))
    )
    (net (code "147") (name "unconnected-(JP40-Pad8)") (class "Default")
      (node (ref "JP40") (pin "8") (pinfunction "8_8") (pintype "passive"))
    )
    (net (code "148") (name "unconnected-(JP40-Pad9)") (class "Default")
      (node (ref "JP40") (pin "9") (pinfunction "9_9") (pintype "passive"))
    )
    (net (code "149") (name "unconnected-(JP40-Pad10)") (class "Default")
      (node (ref "JP40") (pin "10") (pinfunction "10_10") (pintype "passive"))
    )
    (net (code "150") (name "unconnected-(JP40-Pad11)") (class "Default")
      (node (ref "JP40") (pin "11") (pinfunction "11_11") (pintype "passive"))
    )
    (net (code "151") (name "unconnected-(JP40-Pad12)") (class "Default")
      (node (ref "JP40") (pin "12") (pinfunction "12_12") (pintype "passive"))
    )
    (net (code "152") (name "unconnected-(JP40-Pad13)") (class "Default")
      (node (ref "JP40") (pin "13") (pinfunction "13_13") (pintype "passive"))
    )
    (net (code "153") (name "unconnected-(JP40-Pad14)") (class "Default")
      (node (ref "JP40") (pin "14") (pinfunction "14_14") (pintype "passive"))
    )
    (net (code "154") (name "unconnected-(JP40-Pad15)") (class "Default")
      (node (ref "JP40") (pin "15") (pinfunction "15_15") (pintype "passive"))
    )
    (net (code "155") (name "unconnected-(JP40-Pad16)") (class "Default")
      (node (ref "JP40") (pin "16") (pinfunction "16_16") (pintype "passive"))
    )
    (net (code "156") (name "unconnected-(JP41-Pad1)") (class "Default")
      (node (ref "JP41") (pin "1") (pinfunction "1_1") (pintype "passive"))
    )
    (net (code "157") (name "unconnected-(JP41-Pad2)") (class "Default")
      (node (ref "JP41") (pin "2") (pinfunction "2_2") (pintype "passive"))
    )
    (net (code "158") (name "unconnected-(JP41-Pad3)") (class "Default")
      (node (ref "JP41") (pin "3") (pinfunction "3_3") (pintype "passive"))
    )
    (net (code "159") (name "unconnected-(JP41-Pad4)") (class "Default")
      (node (ref "JP41") (pin "4") (pinfunction "4_4") (pintype "passive"))
    )
    (net (code "160") (name "unconnected-(JP41-Pad5)") (class "Default")
      (node (ref "JP41") (pin "5") (pinfunction "5_5") (pintype "passive"))
    )
    (net (code "161") (name "unconnected-(JP41-Pad6)") (class "Default")
      (node (ref "JP41") (pin "6") (pinfunction "6_6") (pintype "passive"))
    )
    (net (code "162") (name "unconnected-(JP41-Pad7)") (class "Default")
      (node (ref "JP41") (pin "7") (pinfunction "7_7") (pintype "passive"))
    )
    (net (code "163") (name "unconnected-(JP41-Pad8)") (class "Default")
      (node (ref "JP41") (pin "8") (pinfunction "8_8") (pintype "passive"))
    )
    (net (code "164") (name "unconnected-(JP41-Pad9)") (class "Default")
      (node (ref "JP41") (pin "9") (pinfunction "9_9") (pintype "passive"))
    )
    (net (code "165") (name "unconnected-(JP41-Pad10)") (class "Default")
      (node (ref "JP41") (pin "10") (pinfunction "10_10") (pintype "passive"))
    )
    (net (code "166") (name "unconnected-(JP41-Pad11)") (class "Default")
      (node (ref "JP41") (pin "11") (pinfunction "11_11") (pintype "passive"))
    )
    (net (code "167") (name "unconnected-(JP41-Pad12)") (class "Default")
      (node (ref "JP41") (pin "12") (pinfunction "12_12") (pintype "passive"))
    )
    (net (code "168") (name "unconnected-(JP41-Pad13)") (class "Default")
      (node (ref "JP41") (pin "13") (pinfunction "13_13") (pintype "passive"))
    )
    (net (code "169") (name "unconnected-(JP41-Pad14)") (class "Default")
      (node (ref "JP41") (pin "14") (pinfunction "14_14") (pintype "passive"))
    )
    (net (code "170") (name "unconnected-(JP41-Pad15)") (class "Default")
      (node (ref "JP41") (pin "15") (pinfunction "15_15") (pintype "passive"))
    )
    (net (code "171") (name "unconnected-(JP41-Pad16)") (class "Default")
      (node (ref "JP41") (pin "16") (pinfunction "16_16") (pintype "passive"))
    )
    (net (code "172") (name "unconnected-(JP42-Pad1)") (class "Default")
      (node (ref "JP42") (pin "1") (pinfunction "1_1") (pintype "passive"))
    )
    (net (code "173") (name "unconnected-(JP42-Pad2)") (class "Default")
      (node (ref "JP42") (pin "2") (pinfunction "2_2") (pintype "passive"))
    )
    (net (code "174") (name "unconnected-(JP42-Pad3)") (class "Default")
      (node (ref "JP42") (pin "3") (pinfunction "3_3") (pintype "passive"))
    )
    (net (code "175") (name "unconnected-(JP42-Pad4)") (class "Default")
      (node (ref "JP42") (pin "4") (pinfunction "4_4") (pintype "passive"))
    )
    (net (code "176") (name "unconnected-(JP42-Pad5)") (class "Default")
      (node (ref "JP42") (pin "5") (pinfunction "5_5") (pintype "passive"))
    )
    (net (code "177") (name "unconnected-(JP42-Pad6)") (class "Default")
      (node (ref "JP42") (pin "6") (pinfunction "6_6") (pintype "passive"))
    )
    (net (code "178") (name "unconnected-(JP42-Pad7)") (class "Default")
      (node (ref "JP42") (pin "7") (pinfunction "7_7") (pintype "passive"))
    )
    (net (code "179") (name "unconnected-(JP42-Pad8)") (class "Default")
      (node (ref "JP42") (pin "8") (pinfunction "8_8") (pintype "passive"))
    )
    (net (code "180") (name "unconnected-(JP42-Pad9)") (class "Default")
      (node (ref "JP42") (pin "9") (pinfunction "9_9") (pintype "passive"))
    )
    (net (code "181") (name "unconnected-(JP42-Pad10)") (class "Default")
      (node (ref "JP42") (pin "10") (pinfunction "10_10") (pintype "passive"))
    )
    (net (code "182") (name "unconnected-(JP42-Pad11)") (class "Default")
      (node (ref "JP42") (pin "11") (pinfunction "11_11") (pintype "passive"))
    )
    (net (code "183") (name "unconnected-(JP42-Pad12)") (class "Default")
      (node (ref "JP42") (pin "12") (pinfunction "12_12") (pintype "passive"))
    )
    (net (code "184") (name "unconnected-(JP42-Pad13)") (class "Default")
      (node (ref "JP42") (pin "13") (pinfunction "13_13") (pintype "passive"))
    )
    (net (code "185") (name "unconnected-(JP42-Pad14)") (class "Default")
      (node (ref "JP42") (pin "14") (pinfunction "14_14") (pintype "passive"))
    )
    (net (code "186") (name "unconnected-(JP42-Pad15)") (class "Default")
      (node (ref "JP42") (pin "15") (pinfunction "15_15") (pintype "passive"))
    )
    (net (code "187") (name "unconnected-(JP42-Pad16)") (class "Default")
      (node (ref "JP42") (pin "16") (pinfunction "16_16") (pintype "passive"))
    )
    (net (code "188") (name "unconnected-(JP43-Pad1)") (class "Default")
      (node (ref "JP43") (pin "1") (pinfunction "1_1") (pintype "passive"))
    )
    (net (code "189") (name "unconnected-(JP43-Pad2)") (class "Default")
      (node (ref "JP43") (pin "2") (pinfunction "2_2") (pintype "passive"))
    )
    (net (code "190") (name "unconnected-(JP43-Pad3)") (class "Default")
      (node (ref "JP43") (pin "3") (pinfunction "3_3") (pintype "passive"))
    )
    (net (code "191") (name "unconnected-(JP43-Pad4)") (class "Default")
      (node (ref "JP43") (pin "4") (pinfunction "4_4") (pintype "passive"))
    )
    (net (code "192") (name "unconnected-(JP43-Pad5)") (class "Default")
      (node (ref "JP43") (pin "5") (pinfunction "5_5") (pintype "passive"))
    )
    (net (code "193") (name "unconnected-(JP43-Pad6)") (class "Default")
      (node (ref "JP43") (pin "6") (pinfunction "6_6") (pintype "passive"))
    )
    (net (code "194") (name "unconnected-(JP43-Pad7)") (class "Default")
      (node (ref "JP43") (pin "7") (pinfunction "7_7") (pintype "passive"))
    )
    (net (code "195") (name "unconnected-(JP43-Pad8)") (class "Default")
      (node (ref "JP43") (pin "8") (pinfunction "8_8") (pintype "passive"))
    )
    (net (code "196") (name "unconnected-(JP43-Pad9)") (class "Default")
      (node (ref "JP43") (pin "9") (pinfunction "9_9") (pintype "passive"))
    )
    (net (code "197") (name "unconnected-(JP43-Pad10)") (class "Default")
      (node (ref "JP43") (pin "10") (pinfunction "10_10") (pintype "passive"))
    )
    (net (code "198") (name "unconnected-(JP43-Pad11)") (class "Default")
      (node (ref "JP43") (pin "11") (pinfunction "11_11") (pintype "passive"))
    )
    (net (code "199") (name "unconnected-(JP43-Pad12)") (class "Default")
      (node (ref "JP43") (pin "12") (pinfunction "12_12") (pintype "passive"))
    )
    (net (code "200") (name "unconnected-(JP43-Pad13)") (class "Default")
      (node (ref "JP43") (pin "13") (pinfunction "13_13") (pintype "passive"))
    )
    (net (code "201") (name "unconnected-(JP43-Pad14)") (class "Default")
      (node (ref "JP43") (pin "14") (pinfunction "14_14") (pintype "passive"))
    )
    (net (code "202") (name "unconnected-(JP43-Pad15)") (class "Default")
      (node (ref "JP43") (pin "15") (pinfunction "15_15") (pintype "passive"))
    )
    (net (code "203") (name "unconnected-(JP43-Pad16)") (class "Default")
      (node (ref "JP43") (pin "16") (pinfunction "16_16") (pintype "passive"))
    )
    (net (code "204") (name "unconnected-(JP44-Pad1)") (class "Default")
      (node (ref "JP44") (pin "1") (pinfunction "1_1") (pintype "passive"))
    )
    (net (code "205") (name "unconnected-(JP44-Pad2)") (class "Default")
      (node (ref "JP44") (pin "2") (pinfunction "2_2") (pintype "passive"))
    )
    (net (code "206") (name "unconnected-(JP44-Pad3)") (class "Default")
      (node (ref "JP44") (pin "3") (pinfunction "3_3") (pintype "passive"))
    )
    (net (code "207") (name "unconnected-(JP44-Pad4)") (class "Default")
      (node (ref "JP44") (pin "4") (pinfunction "4_4") (pintype "passive"))
    )
    (net (code "208") (name "unconnected-(JP44-Pad5)") (class "Default")
      (node (ref "JP44") (pin "5") (pinfunction "5_5") (pintype "passive"))
    )
    (net (code "209") (name "unconnected-(JP44-Pad6)") (class "Default")
      (node (ref "JP44") (pin "6") (pinfunction "6_6") (pintype "passive"))
    )
    (net (code "210") (name "unconnected-(JP44-Pad7)") (class "Default")
      (node (ref "JP44") (pin "7") (pinfunction "7_7") (pintype "passive"))
    )
    (net (code "211") (name "unconnected-(JP44-Pad8)") (class "Default")
      (node (ref "JP44") (pin "8") (pinfunction "8_8") (pintype "passive"))
    )
    (net (code "212") (name "unconnected-(JP44-Pad9)") (class "Default")
      (node (ref "JP44") (pin "9") (pinfunction "9_9") (pintype "passive"))
    )
    (net (code "213") (name "unconnected-(JP44-Pad10)") (class "Default")
      (node (ref "JP44") (pin "10") (pinfunction "10_10") (pintype "passive"))
    )
    (net (code "214") (name "unconnected-(JP44-Pad11)") (class "Default")
      (node (ref "JP44") (pin "11") (pinfunction "11_11") (pintype "passive"))
    )
    (net (code "215") (name "unconnected-(JP44-Pad12)") (class "Default")
      (node (ref "JP44") (pin "12") (pinfunction "12_12") (pintype "passive"))
    )
    (net (code "216") (name "unconnected-(JP44-Pad13)") (class "Default")
      (node (ref "JP44") (pin "13") (pinfunction "13_13") (pintype "passive"))
    )
    (net (code "217") (name "unconnected-(JP44-Pad14)") (class "Default")
      (node (ref "JP44") (pin "14") (pinfunction "14_14") (pintype "passive"))
    )
    (net (code "218") (name "unconnected-(JP44-Pad15)") (class "Default")
      (node (ref "JP44") (pin "15") (pinfunction "15_15") (pintype "passive"))
    )
    (net (code "219") (name "unconnected-(JP44-Pad16)") (class "Default")
      (node (ref "JP44") (pin "16") (pinfunction "16_16") (pintype "passive"))
    )
    (net (code "220") (name "unconnected-(JP45-Pad1)") (class "Default")
      (node (ref "JP45") (pin "1") (pinfunction "1_1") (pintype "passive"))
    )
    (net (code "221") (name "unconnected-(JP45-Pad2)") (class "Default")
      (node (ref "JP45") (pin "2") (pinfunction "2_2") (pintype "passive"))
    )
    (net (code "222") (name "unconnected-(JP45-Pad3)") (class "Default")
      (node (ref "JP45") (pin "3") (pinfunction "3_3") (pintype "passive"))
    )
    (net (code "223") (name "unconnected-(JP45-Pad4)") (class "Default")
      (node (ref "JP45") (pin "4") (pinfunction "4_4") (pintype "passive"))
    )
    (net (code "224") (name "unconnected-(JP45-Pad5)") (class "Default")
      (node (ref "JP45") (pin "5") (pinfunction "5_5") (pintype "passive"))
    )
    (net (code "225") (name "unconnected-(JP45-Pad6)") (class "Default")
      (node (ref "JP45") (pin "6") (pinfunction "6_6") (pintype "passive"))
    )
    (net (code "226") (name "unconnected-(JP45-Pad7)") (class "Default")
      (node (ref "JP45") (pin "7") (pinfunction "7_7") (pintype "passive"))
    )
    (net (code "227") (name "unconnected-(JP45-Pad8)") (class "Default")
      (node (ref "JP45") (pin "8") (pinfunction "8_8") (pintype "passive"))
    )
    (net (code "228") (name "unconnected-(JP45-Pad9)") (class "Default")
      (node (ref "JP45") (pin "9") (pinfunction "9_9") (pintype "passive"))
    )
    (net (code "229") (name "unconnected-(JP45-Pad10)") (class "Default")
      (node (ref "JP45") (pin "10") (pinfunction "10_10") (pintype "passive"))
    )
    (net (code "230") (name "unconnected-(JP45-Pad11)") (class "Default")
      (node (ref "JP45") (pin "11") (pinfunction "11_11") (pintype "passive"))
    )
    (net (code "231") (name "unconnected-(JP45-Pad12)") (class "Default")
      (node (ref "JP45") (pin "12") (pinfunction "12_12") (pintype "passive"))
    )
    (net (code "232") (name "unconnected-(JP45-Pad13)") (class "Default")
      (node (ref "JP45") (pin "13") (pinfunction "13_13") (pintype "passive"))
    )
    (net (code "233") (name "unconnected-(JP45-Pad14)") (class "Default")
      (node (ref "JP45") (pin "14") (pinfunction "14_14") (pintype "passive"))
    )
    (net (code "234") (name "unconnected-(JP45-Pad15)") (class "Default")
      (node (ref "JP45") (pin "15") (pinfunction "15_15") (pintype "passive"))
    )
    (net (code "235") (name "unconnected-(JP45-Pad16)") (class "Default")
      (node (ref "JP45") (pin "16") (pinfunction "16_16") (pintype "passive"))
    )
    (net (code "236") (name "unconnected-(JP46-Pad1)") (class "Default")
      (node (ref "JP46") (pin "1") (pinfunction "1_1") (pintype "passive"))
    )
    (net (code "237") (name "unconnected-(JP46-Pad2)") (class "Default")
      (node (ref "JP46") (pin "2") (pinfunction "2_2") (pintype "passive"))
    )
    (net (code "238") (name "unconnected-(JP46-Pad3)") (class "Default")
      (node (ref "JP46") (pin "3") (pinfunction "3_3") (pintype "passive"))
    )
    (net (code "239") (name "unconnected-(JP46-Pad4)") (class "Default")
      (node (ref "JP46") (pin "4") (pinfunction "4_4") (pintype "passive"))
    )
    (net (code "240") (name "unconnected-(JP46-Pad5)") (class "Default")
      (node (ref "JP46") (pin "5") (pinfunction "5_5") (pintype "passive"))
    )
    (net (code "241") (name "unconnected-(JP46-Pad6)") (class "Default")
      (node (ref "JP46") (pin "6") (pinfunction "6_6") (pintype "passive"))
    )
    (net (code "242") (name "unconnected-(JP46-Pad7)") (class "Default")
      (node (ref "JP46") (pin "7") (pinfunction "7_7") (pintype "passive"))
    )
    (net (code "243") (name "unconnected-(JP46-Pad8)") (class "Default")
      (node (ref "JP46") (pin "8") (pinfunction "8_8") (pintype "passive"))
    )
    (net (code "244") (name "unconnected-(JP46-Pad9)") (class "Default")
      (node (ref "JP46") (pin "9") (pinfunction "9_9") (pintype "passive"))
    )
    (net (code "245") (name "unconnected-(JP46-Pad10)") (class "Default")
      (node (ref "JP46") (pin "10") (pinfunction "10_10") (pintype "passive"))
    )
    (net (code "246") (name "unconnected-(JP46-Pad11)") (class "Default")
      (node (ref "JP46") (pin "11") (pinfunction "11_11") (pintype "passive"))
    )
    (net (code "247") (name "unconnected-(JP46-Pad12)") (class "Default")
      (node (ref "JP46") (pin "12") (pinfunction "12_12") (pintype "passive"))
    )
    (net (code "248") (name "unconnected-(JP46-Pad13)") (class "Default")
      (node (ref "JP46") (pin "13") (pinfunction "13_13") (pintype "passive"))
    )
    (net (code "249") (name "unconnected-(JP46-Pad14)") (class "Default")
      (node (ref "JP46") (pin "14") (pinfunction "14_14") (pintype "passive"))
    )
    (net (code "250") (name "unconnected-(JP46-Pad15)") (class "Default")
      (node (ref "JP46") (pin "15") (pinfunction "15_15") (pintype "passive"))
    )
    (net (code "251") (name "unconnected-(JP46-Pad16)") (class "Default")
      (node (ref "JP46") (pin "16") (pinfunction "16_16") (pintype "passive"))
    )
    (net (code "252") (name "unconnected-(JP47-Pad1)") (class "Default")
      (node (ref "JP47") (pin "1") (pinfunction "1_1") (pintype "passive"))
    )
    (net (code "253") (name "unconnected-(JP47-Pad2)") (class "Default")
      (node (ref "JP47") (pin "2") (pinfunction "2_2") (pintype "passive"))
    )
    (net (code "254") (name "unconnected-(JP47-Pad3)") (class "Default")
      (node (ref "JP47") (pin "3") (pinfunction "3_3") (pintype "passive"))
    )
    (net (code "255") (name "unconnected-(JP47-Pad4)") (class "Default")
      (node (ref "JP47") (pin "4") (pinfunction "4_4") (pintype "passive"))
    )
    (net (code "256") (name "unconnected-(JP47-Pad5)") (class "Default")
      (node (ref "JP47") (pin "5") (pinfunction "5_5") (pintype "passive"))
    )
    (net (code "257") (name "unconnected-(JP47-Pad6)") (class "Default")
      (node (ref "JP47") (pin "6") (pinfunction "6_6") (pintype "passive"))
    )
    (net (code "258") (name "unconnected-(JP47-Pad7)") (class "Default")
      (node (ref "JP47") (pin "7") (pinfunction "7_7") (pintype "passive"))
    )
    (net (code "259") (name "unconnected-(JP47-Pad8)") (class "Default")
      (node (ref "JP47") (pin "8") (pinfunction "8_8") (pintype "passive"))
    )
    (net (code "260") (name "unconnected-(JP47-Pad9)") (class "Default")
      (node (ref "JP47") (pin "9") (pinfunction "9_9") (pintype "passive"))
    )
    (net (code "261") (name "unconnected-(JP47-Pad10)") (class "Default")
      (node (ref "JP47") (pin "10") (pinfunction "10_10") (pintype "passive"))
    )
    (net (code "262") (name "unconnected-(JP47-Pad11)") (class "Default")
      (node (ref "JP47") (pin "11") (pinfunction "11_11") (pintype "passive"))
    )
    (net (code "263") (name "unconnected-(JP47-Pad12)") (class "Default")
      (node (ref "JP47") (pin "12") (pinfunction "12_12") (pintype "passive"))
    )
    (net (code "264") (name "unconnected-(JP47-Pad13)") (class "Default")
      (node (ref "JP47") (pin "13") (pinfunction "13_13") (pintype "passive"))
    )
    (net (code "265") (name "unconnected-(JP47-Pad14)") (class "Default")
      (node (ref "JP47") (pin "14") (pinfunction "14_14") (pintype "passive"))
    )
    (net (code "266") (name "unconnected-(JP47-Pad15)") (class "Default")
      (node (ref "JP47") (pin "15") (pinfunction "15_15") (pintype "passive"))
    )
    (net (code "267") (name "unconnected-(JP47-Pad16)") (class "Default")
      (node (ref "JP47") (pin "16") (pinfunction "16_16") (pintype "passive"))
    )
    (net (code "268") (name "unconnected-(JP48-Pad1)") (class "Default")
      (node (ref "JP48") (pin "1") (pinfunction "1_1") (pintype "passive"))
    )
    (net (code "269") (name "unconnected-(JP48-Pad2)") (class "Default")
      (node (ref "JP48") (pin "2") (pinfunction "2_2") (pintype "passive"))
    )
    (net (code "270") (name "unconnected-(JP48-Pad3)") (class "Default")
      (node (ref "JP48") (pin "3") (pinfunction "3_3") (pintype "passive"))
    )
    (net (code "271") (name "unconnected-(JP48-Pad4)") (class "Default")
      (node (ref "JP48") (pin "4") (pinfunction "4_4") (pintype "passive"))
    )
    (net (code "272") (name "unconnected-(JP48-Pad5)") (class "Default")
      (node (ref "JP48") (pin "5") (pinfunction "5_5") (pintype "passive"))
    )
    (net (code "273") (name "unconnected-(JP48-Pad6)") (class "Default")
      (node (ref "JP48") (pin "6") (pinfunction "6_6") (pintype "passive"))
    )
    (net (code "274") (name "unconnected-(JP48-Pad7)") (class "Default")
      (node (ref "JP48") (pin "7") (pinfunction "7_7") (pintype "passive"))
    )
    (net (code "275") (name "unconnected-(JP48-Pad8)") (class "Default")
      (node (ref "JP48") (pin "8") (pinfunction "8_8") (pintype "passive"))
    )
    (net (code "276") (name "unconnected-(JP48-Pad9)") (class "Default")
      (node (ref "JP48") (pin "9") (pinfunction "9_9") (pintype "passive"))
    )
    (net (code "277") (name "unconnected-(JP48-Pad10)") (class "Default")
      (node (ref "JP48") (pin "10") (pinfunction "10_10") (pintype "passive"))
    )
    (net (code "278") (name "unconnected-(JP48-Pad11)") (class "Default")
      (node (ref "JP48") (pin "11") (pinfunction "11_11") (pintype "passive"))
    )
    (net (code "279") (name "unconnected-(JP48-Pad12)") (class "Default")
      (node (ref "JP48") (pin "12") (pinfunction "12_12") (pintype "passive"))
    )
    (net (code "280") (name "unconnected-(JP48-Pad13)") (class "Default")
      (node (ref "JP48") (pin "13") (pinfunction "13_13") (pintype "passive"))
    )
    (net (code "281") (name "unconnected-(JP48-Pad14)") (class "Default")
      (node (ref "JP48") (pin "14") (pinfunction "14_14") (pintype "passive"))
    )
    (net (code "282") (name "unconnected-(JP48-Pad15)") (class "Default")
      (node (ref "JP48") (pin "15") (pinfunction "15_15") (pintype "passive"))
    )
    (net (code "283") (name "unconnected-(JP48-Pad16)") (class "Default")
      (node (ref "JP48") (pin "16") (pinfunction "16_16") (pintype "passive"))
    )
    (net (code "284") (name "unconnected-(JP49-Pad1)") (class "Default")
      (node (ref "JP49") (pin "1") (pinfunction "1_1") (pintype "passive"))
    )
    (net (code "285") (name "unconnected-(JP49-Pad2)") (class "Default")
      (node (ref "JP49") (pin "2") (pinfunction "2_2") (pintype "passive"))
    )
    (net (code "286") (name "unconnected-(JP49-Pad3)") (class "Default")
      (node (ref "JP49") (pin "3") (pinfunction "3_3") (pintype "passive"))
    )
    (net (code "287") (name "unconnected-(JP49-Pad4)") (class "Default")
      (node (ref "JP49") (pin "4") (pinfunction "4_4") (pintype "passive"))
    )
    (net (code "288") (name "unconnected-(JP49-Pad5)") (class "Default")
      (node (ref "JP49") (pin "5") (pinfunction "5_5") (pintype "passive"))
    )
    (net (code "289") (name "unconnected-(JP49-Pad6)") (class "Default")
      (node (ref "JP49") (pin "6") (pinfunction "6_6") (pintype "passive"))
    )
    (net (code "290") (name "unconnected-(JP49-Pad7)") (class "Default")
      (node (ref "JP49") (pin "7") (pinfunction "7_7") (pintype "passive"))
    )
    (net (code "291") (name "unconnected-(JP49-Pad8)") (class "Default")
      (node (ref "JP49") (pin "8") (pinfunction "8_8") (pintype "passive"))
    )
    (net (code "292") (name "unconnected-(JP49-Pad9)") (class "Default")
      (node (ref "JP49") (pin "9") (pinfunction "9_9") (pintype "passive"))
    )
    (net (code "293") (name "unconnected-(JP49-Pad10)") (class "Default")
      (node (ref "JP49") (pin "10") (pinfunction "10_10") (pintype "passive"))
    )
    (net (code "294") (name "unconnected-(JP49-Pad11)") (class "Default")
      (node (ref "JP49") (pin "11") (pinfunction "11_11") (pintype "passive"))
    )
    (net (code "295") (name "unconnected-(JP49-Pad12)") (class "Default")
      (node (ref "JP49") (pin "12") (pinfunction "12_12") (pintype "passive"))
    )
    (net (code "296") (name "unconnected-(JP49-Pad13)") (class "Default")
      (node (ref "JP49") (pin "13") (pinfunction "13_13") (pintype "passive"))
    )
    (net (code "297") (name "unconnected-(JP49-Pad14)") (class "Default")
      (node (ref "JP49") (pin "14") (pinfunction "14_14") (pintype "passive"))
    )
    (net (code "298") (name "unconnected-(JP49-Pad15)") (class "Default")
      (node (ref "JP49") (pin "15") (pinfunction "15_15") (pintype "passive"))
    )
    (net (code "299") (name "unconnected-(JP49-Pad16)") (class "Default")
      (node (ref "JP49") (pin "16") (pinfunction "16_16") (pintype "passive"))
    )
    (net (code "300") (name "unconnected-(JP50-Pad1)") (class "Default")
      (node (ref "JP50") (pin "1") (pinfunction "1_1") (pintype "passive"))
    )
    (net (code "301") (name "unconnected-(JP50-Pad2)") (class "Default")
      (node (ref "JP50") (pin "2") (pinfunction "2_2") (pintype "passive"))
    )
    (net (code "302") (name "unconnected-(JP50-Pad3)") (class "Default")
      (node (ref "JP50") (pin "3") (pinfunction "3_3") (pintype "passive"))
    )
    (net (code "303") (name "unconnected-(JP50-Pad4)") (class "Default")
      (node (ref "JP50") (pin "4") (pinfunction "4_4") (pintype "passive"))
    )
    (net (code "304") (name "unconnected-(JP50-Pad5)") (class "Default")
      (node (ref "JP50") (pin "5") (pinfunction "5_5") (pintype "passive"))
    )
    (net (code "305") (name "unconnected-(JP50-Pad6)") (class "Default")
      (node (ref "JP50") (pin "6") (pinfunction "6_6") (pintype "passive"))
    )
    (net (code "306") (name "unconnected-(JP50-Pad7)") (class "Default")
      (node (ref "JP50") (pin "7") (pinfunction "7_7") (pintype "passive"))
    )
    (net (code "307") (name "unconnected-(JP50-Pad8)") (class "Default")
      (node (ref "JP50") (pin "8") (pinfunction "8_8") (pintype "passive"))
    )
    (net (code "308") (name "unconnected-(JP50-Pad9)") (class "Default")
      (node (ref "JP50") (pin "9") (pinfunction "9_9") (pintype "passive"))
    )
    (net (code "309") (name "unconnected-(JP50-Pad10)") (class "Default")
      (node (ref "JP50") (pin "10") (pinfunction "10_10") (pintype "passive"))
    )
    (net (code "310") (name "unconnected-(JP50-Pad11)") (class "Default")
      (node (ref "JP50") (pin "11") (pinfunction "11_11") (pintype "passive"))
    )
    (net (code "311") (name "unconnected-(JP50-Pad12)") (class "Default")
      (node (ref "JP50") (pin "12") (pinfunction "12_12") (pintype "passive"))
    )
    (net (code "312") (name "unconnected-(JP50-Pad13)") (class "Default")
      (node (ref "JP50") (pin "13") (pinfunction "13_13") (pintype "passive"))
    )
    (net (code "313") (name "unconnected-(JP50-Pad14)") (class "Default")
      (node (ref "JP50") (pin "14") (pinfunction "14_14") (pintype "passive"))
    )
    (net (code "314") (name "unconnected-(JP50-Pad15)") (class "Default")
      (node (ref "JP50") (pin "15") (pinfunction "15_15") (pintype "passive"))
    )
    (net (code "315") (name "unconnected-(JP50-Pad16)") (class "Default")
      (node (ref "JP50") (pin "16") (pinfunction "16_16") (pintype "passive"))
    )
    (net (code "316") (name "unconnected-(JP51-Pad1)") (class "Default")
      (node (ref "JP51") (pin "1") (pinfunction "1_1") (pintype "passive"))
    )
    (net (code "317") (name "unconnected-(JP51-Pad2)") (class "Default")
      (node (ref "JP51") (pin "2") (pinfunction "2_2") (pintype "passive"))
    )
    (net (code "318") (name "unconnected-(JP51-Pad3)") (class "Default")
      (node (ref "JP51") (pin "3") (pinfunction "3_3") (pintype "passive"))
    )
    (net (code "319") (name "unconnected-(JP51-Pad4)") (class "Default")
      (node (ref "JP51") (pin "4") (pinfunction "4_4") (pintype "passive"))
    )
    (net (code "320") (name "unconnected-(JP51-Pad5)") (class "Default")
      (node (ref "JP51") (pin "5") (pinfunction "5_5") (pintype "passive"))
    )
    (net (code "321") (name "unconnected-(JP51-Pad6)") (class "Default")
      (node (ref "JP51") (pin "6") (pinfunction "6_6") (pintype "passive"))
    )
    (net (code "322") (name "unconnected-(JP51-Pad7)") (class "Default")
      (node (ref "JP51") (pin "7") (pinfunction "7_7") (pintype "passive"))
    )
    (net (code "323") (name "unconnected-(JP51-Pad8)") (class "Default")
      (node (ref "JP51") (pin "8") (pinfunction "8_8") (pintype "passive"))
    )
    (net (code "324") (name "unconnected-(JP51-Pad9)") (class "Default")
      (node (ref "JP51") (pin "9") (pinfunction "9_9") (pintype "passive"))
    )
    (net (code "325") (name "unconnected-(JP51-Pad10)") (class "Default")
      (node (ref "JP51") (pin "10") (pinfunction "10_10") (pintype "passive"))
    )
    (net (code "326") (name "unconnected-(JP51-Pad11)") (class "Default")
      (node (ref "JP51") (pin "11") (pinfunction "11_11") (pintype "passive"))
    )
    (net (code "327") (name "unconnected-(JP51-Pad12)") (class "Default")
      (node (ref "JP51") (pin "12") (pinfunction "12_12") (pintype "passive"))
    )
    (net (code "328") (name "unconnected-(JP51-Pad13)") (class "Default")
      (node (ref "JP51") (pin "13") (pinfunction "13_13") (pintype "passive"))
    )
    (net (code "329") (name "unconnected-(JP51-Pad14)") (class "Default")
      (node (ref "JP51") (pin "14") (pinfunction "14_14") (pintype "passive"))
    )
    (net (code "330") (name "unconnected-(JP51-Pad15)") (class "Default")
      (node (ref "JP51") (pin "15") (pinfunction "15_15") (pintype "passive"))
    )
    (net (code "331") (name "unconnected-(JP51-Pad16)") (class "Default")
      (node (ref "JP51") (pin "16") (pinfunction "16_16") (pintype "passive"))
    )
    (net (code "332") (name "unconnected-(JP52-Pad1)") (class "Default")
      (node (ref "JP52") (pin "1") (pinfunction "1_1") (pintype "passive"))
    )
    (net (code "333") (name "unconnected-(JP52-Pad2)") (class "Default")
      (node (ref "JP52") (pin "2") (pinfunction "2_2") (pintype "passive"))
    )
    (net (code "334") (name "unconnected-(JP52-Pad3)") (class "Default")
      (node (ref "JP52") (pin "3") (pinfunction "3_3") (pintype "passive"))
    )
    (net (code "335") (name "unconnected-(JP52-Pad4)") (class "Default")
      (node (ref "JP52") (pin "4") (pinfunction "4_4") (pintype "passive"))
    )
    (net (code "336") (name "unconnected-(JP52-Pad5)") (class "Default")
      (node (ref "JP52") (pin "5") (pinfunction "5_5") (pintype "passive"))
    )
    (net (code "337") (name "unconnected-(JP52-Pad6)") (class "Default")
      (node (ref "JP52") (pin "6") (pinfunction "6_6") (pintype "passive"))
    )
    (net (code "338") (name "unconnected-(JP52-Pad7)") (class "Default")
      (node (ref "JP52") (pin "7") (pinfunction "7_7") (pintype "passive"))
    )
    (net (code "339") (name "unconnected-(JP52-Pad8)") (class "Default")
      (node (ref "JP52") (pin "8") (pinfunction "8_8") (pintype "passive"))
    )
    (net (code "340") (name "unconnected-(JP52-Pad9)") (class "Default")
      (node (ref "JP52") (pin "9") (pinfunction "9_9") (pintype "passive"))
    )
    (net (code "341") (name "unconnected-(JP52-Pad10)") (class "Default")
      (node (ref "JP52") (pin "10") (pinfunction "10_10") (pintype "passive"))
    )
    (net (code "342") (name "unconnected-(JP52-Pad11)") (class "Default")
      (node (ref "JP52") (pin "11") (pinfunction "11_11") (pintype "passive"))
    )
    (net (code "343") (name "unconnected-(JP52-Pad12)") (class "Default")
      (node (ref "JP52") (pin "12") (pinfunction "12_12") (pintype "passive"))
    )
    (net (code "344") (name "unconnected-(JP52-Pad13)") (class "Default")
      (node (ref "JP52") (pin "13") (pinfunction "13_13") (pintype "passive"))
    )
    (net (code "345") (name "unconnected-(JP52-Pad14)") (class "Default")
      (node (ref "JP52") (pin "14") (pinfunction "14_14") (pintype "passive"))
    )
    (net (code "346") (name "unconnected-(JP52-Pad15)") (class "Default")
      (node (ref "JP52") (pin "15") (pinfunction "15_15") (pintype "passive"))
    )
    (net (code "347") (name "unconnected-(JP52-Pad16)") (class "Default")
      (node (ref "JP52") (pin "16") (pinfunction "16_16") (pintype "passive"))
    )
    (net (code "348") (name "unconnected-(JP53-Pad1)") (class "Default")
      (node (ref "JP53") (pin "1") (pinfunction "1_1") (pintype "passive"))
    )
    (net (code "349") (name "unconnected-(JP53-Pad2)") (class "Default")
      (node (ref "JP53") (pin "2") (pinfunction "2_2") (pintype "passive"))
    )
    (net (code "350") (name "unconnected-(JP53-Pad3)") (class "Default")
      (node (ref "JP53") (pin "3") (pinfunction "3_3") (pintype "passive"))
    )
    (net (code "351") (name "unconnected-(JP53-Pad4)") (class "Default")
      (node (ref "JP53") (pin "4") (pinfunction "4_4") (pintype "passive"))
    )
    (net (code "352") (name "unconnected-(JP53-Pad5)") (class "Default")
      (node (ref "JP53") (pin "5") (pinfunction "5_5") (pintype "passive"))
    )
    (net (code "353") (name "unconnected-(JP53-Pad6)") (class "Default")
      (node (ref "JP53") (pin "6") (pinfunction "6_6") (pintype "passive"))
    )
    (net (code "354") (name "unconnected-(JP53-Pad7)") (class "Default")
      (node (ref "JP53") (pin "7") (pinfunction "7_7") (pintype "passive"))
    )
    (net (code "355") (name "unconnected-(JP53-Pad8)") (class "Default")
      (node (ref "JP53") (pin "8") (pinfunction "8_8") (pintype "passive"))
    )
    (net (code "356") (name "unconnected-(JP53-Pad9)") (class "Default")
      (node (ref "JP53") (pin "9") (pinfunction "9_9") (pintype "passive"))
    )
    (net (code "357") (name "unconnected-(JP53-Pad10)") (class "Default")
      (node (ref "JP53") (pin "10") (pinfunction "10_10") (pintype "passive"))
    )
    (net (code "358") (name "unconnected-(JP53-Pad11)") (class "Default")
      (node (ref "JP53") (pin "11") (pinfunction "11_11") (pintype "passive"))
    )
    (net (code "359") (name "unconnected-(JP53-Pad12)") (class "Default")
      (node (ref "JP53") (pin "12") (pinfunction "12_12") (pintype "passive"))
    )
    (net (code "360") (name "unconnected-(JP53-Pad13)") (class "Default")
      (node (ref "JP53") (pin "13") (pinfunction "13_13") (pintype "passive"))
    )
    (net (code "361") (name "unconnected-(JP53-Pad14)") (class "Default")
      (node (ref "JP53") (pin "14") (pinfunction "14_14") (pintype "passive"))
    )
    (net (code "362") (name "unconnected-(JP53-Pad15)") (class "Default")
      (node (ref "JP53") (pin "15") (pinfunction "15_15") (pintype "passive"))
    )
    (net (code "363") (name "unconnected-(JP53-Pad16)") (class "Default")
      (node (ref "JP53") (pin "16") (pinfunction "16_16") (pintype "passive"))
    )
    (net (code "364") (name "unconnected-(JP54-Pad1)") (class "Default")
      (node (ref "JP54") (pin "1") (pinfunction "1_1") (pintype "passive"))
    )
    (net (code "365") (name "unconnected-(JP54-Pad2)") (class "Default")
      (node (ref "JP54") (pin "2") (pinfunction "2_2") (pintype "passive"))
    )
    (net (code "366") (name "unconnected-(JP54-Pad3)") (class "Default")
      (node (ref "JP54") (pin "3") (pinfunction "3_3") (pintype "passive"))
    )
    (net (code "367") (name "unconnected-(JP54-Pad4)") (class "Default")
      (node (ref "JP54") (pin "4") (pinfunction "4_4") (pintype "passive"))
    )
    (net (code "368") (name "unconnected-(JP54-Pad5)") (class "Default")
      (node (ref "JP54") (pin "5") (pinfunction "5_5") (pintype "passive"))
    )
    (net (code "369") (name "unconnected-(JP54-Pad6)") (class "Default")
      (node (ref "JP54") (pin "6") (pinfunction "6_6") (pintype "passive"))
    )
    (net (code "370") (name "unconnected-(JP54-Pad7)") (class "Default")
      (node (ref "JP54") (pin "7") (pinfunction "7_7") (pintype "passive"))
    )
    (net (code "371") (name "unconnected-(JP54-Pad8)") (class "Default")
      (node (ref "JP54") (pin "8") (pinfunction "8_8") (pintype "passive"))
    )
    (net (code "372") (name "unconnected-(JP54-Pad9)") (class "Default")
      (node (ref "JP54") (pin "9") (pinfunction "9_9") (pintype "passive"))
    )
    (net (code "373") (name "unconnected-(JP54-Pad10)") (class "Default")
      (node (ref "JP54") (pin "10") (pinfunction "10_10") (pintype "passive"))
    )
    (net (code "374") (name "unconnected-(JP54-Pad11)") (class "Default")
      (node (ref "JP54") (pin "11") (pinfunction "11_11") (pintype "passive"))
    )
    (net (code "375") (name "unconnected-(JP54-Pad12)") (class "Default")
      (node (ref "JP54") (pin "12") (pinfunction "12_12") (pintype "passive"))
    )
    (net (code "376") (name "unconnected-(JP54-Pad13)") (class "Default")
      (node (ref "JP54") (pin "13") (pinfunction "13_13") (pintype "passive"))
    )
    (net (code "377") (name "unconnected-(JP54-Pad14)") (class "Default")
      (node (ref "JP54") (pin "14") (pinfunction "14_14") (pintype "passive"))
    )
    (net (code "378") (name "unconnected-(JP54-Pad15)") (class "Default")
      (node (ref "JP54") (pin "15") (pinfunction "15_15") (pintype "passive"))
    )
    (net (code "379") (name "unconnected-(JP54-Pad16)") (class "Default")
      (node (ref "JP54") (pin "16") (pinfunction "16_16") (pintype "passive"))
    )
    (net (code "380") (name "unconnected-(JP55-Pad1)") (class "Default")
      (node (ref "JP55") (pin "1") (pinfunction "1_1") (pintype "passive"))
    )
    (net (code "381") (name "unconnected-(JP55-Pad2)") (class "Default")
      (node (ref "JP55") (pin "2") (pinfunction "2_2") (pintype "passive"))
    )
    (net (code "382") (name "unconnected-(JP55-Pad3)") (class "Default")
      (node (ref "JP55") (pin "3") (pinfunction "3_3") (pintype "passive"))
    )
    (net (code "383") (name "unconnected-(JP55-Pad4)") (class "Default")
      (node (ref "JP55") (pin "4") (pinfunction "4_4") (pintype "passive"))
    )
    (net (code "384") (name "unconnected-(JP55-Pad5)") (class "Default")
      (node (ref "JP55") (pin "5") (pinfunction "5_5") (pintype "passive"))
    )
    (net (code "385") (name "unconnected-(JP55-Pad6)") (class "Default")
      (node (ref "JP55") (pin "6") (pinfunction "6_6") (pintype "passive"))
    )
    (net (code "386") (name "unconnected-(JP55-Pad7)") (class "Default")
      (node (ref "JP55") (pin "7") (pinfunction "7_7") (pintype "passive"))
    )
    (net (code "387") (name "unconnected-(JP55-Pad8)") (class "Default")
      (node (ref "JP55") (pin "8") (pinfunction "8_8") (pintype "passive"))
    )
    (net (code "388") (name "unconnected-(JP55-Pad9)") (class "Default")
      (node (ref "JP55") (pin "9") (pinfunction "9_9") (pintype "passive"))
    )
    (net (code "389") (name "unconnected-(JP55-Pad10)") (class "Default")
      (node (ref "JP55") (pin "10") (pinfunction "10_10") (pintype "passive"))
    )
    (net (code "390") (name "unconnected-(JP55-Pad11)") (class "Default")
      (node (ref "JP55") (pin "11") (pinfunction "11_11") (pintype "passive"))
    )
    (net (code "391") (name "unconnected-(JP55-Pad12)") (class "Default")
      (node (ref "JP55") (pin "12") (pinfunction "12_12") (pintype "passive"))
    )
    (net (code "392") (name "unconnected-(JP55-Pad13)") (class "Default")
      (node (ref "JP55") (pin "13") (pinfunction "13_13") (pintype "passive"))
    )
    (net (code "393") (name "unconnected-(JP55-Pad14)") (class "Default")
      (node (ref "JP55") (pin "14") (pinfunction "14_14") (pintype "passive"))
    )
    (net (code "394") (name "unconnected-(JP55-Pad15)") (class "Default")
      (node (ref "JP55") (pin "15") (pinfunction "15_15") (pintype "passive"))
    )
    (net (code "395") (name "unconnected-(JP55-Pad16)") (class "Default")
      (node (ref "JP55") (pin "16") (pinfunction "16_16") (pintype "passive"))
    )
    (net (code "396") (name "unconnected-(JP56-Pad1)") (class "Default")
      (node (ref "JP56") (pin "1") (pinfunction "1_1") (pintype "passive"))
    )
    (net (code "397") (name "unconnected-(JP56-Pad2)") (class "Default")
      (node (ref "JP56") (pin "2") (pinfunction "2_2") (pintype "passive"))
    )
    (net (code "398") (name "unconnected-(JP56-Pad3)") (class "Default")
      (node (ref "JP56") (pin "3") (pinfunction "3_3") (pintype "passive"))
    )
    (net (code "399") (name "unconnected-(JP56-Pad4)") (class "Default")
      (node (ref "JP56") (pin "4") (pinfunction "4_4") (pintype "passive"))
    )
    (net (code "400") (name "unconnected-(JP56-Pad5)") (class "Default")
      (node (ref "JP56") (pin "5") (pinfunction "5_5") (pintype "passive"))
    )
    (net (code "401") (name "unconnected-(JP56-Pad6)") (class "Default")
      (node (ref "JP56") (pin "6") (pinfunction "6_6") (pintype "passive"))
    )
    (net (code "402") (name "unconnected-(JP56-Pad7)") (class "Default")
      (node (ref "JP56") (pin "7") (pinfunction "7_7") (pintype "passive"))
    )
    (net (code "403") (name "unconnected-(JP56-Pad8)") (class "Default")
      (node (ref "JP56") (pin "8") (pinfunction "8_8") (pintype "passive"))
    )
    (net (code "404") (name "unconnected-(JP56-Pad9)") (class "Default")
      (node (ref "JP56") (pin "9") (pinfunction "9_9") (pintype "passive"))
    )
    (net (code "405") (name "unconnected-(JP56-Pad10)") (class "Default")
      (node (ref "JP56") (pin "10") (pinfunction "10_10") (pintype "passive"))
    )
    (net (code "406") (name "unconnected-(JP56-Pad11)") (class "Default")
      (node (ref "JP56") (pin "11") (pinfunction "11_11") (pintype "passive"))
    )
    (net (code "407") (name "unconnected-(JP56-Pad12)") (class "Default")
      (node (ref "JP56") (pin "12") (pinfunction "12_12") (pintype "passive"))
    )
    (net (code "408") (name "unconnected-(JP56-Pad13)") (class "Default")
      (node (ref "JP56") (pin "13") (pinfunction "13_13") (pintype "passive"))
    )
    (net (code "409") (name "unconnected-(JP56-Pad14)") (class "Default")
      (node (ref "JP56") (pin "14") (pinfunction "14_14") (pintype "passive"))
    )
    (net (code "410") (name "unconnected-(JP56-Pad15)") (class "Default")
      (node (ref "JP56") (pin "15") (pinfunction "15_15") (pintype "passive"))
    )
    (net (code "411") (name "unconnected-(JP56-Pad16)") (class "Default")
      (node (ref "JP56") (pin "16") (pinfunction "16_16") (pintype "passive"))
    )
    (net (code "412") (name "unconnected-(JP57-Pad1)") (class "Default")
      (node (ref "JP57") (pin "1") (pinfunction "1_1") (pintype "passive"))
    )
    (net (code "413") (name "unconnected-(JP57-Pad2)") (class "Default")
      (node (ref "JP57") (pin "2") (pinfunction "2_2") (pintype "passive"))
    )
    (net (code "414") (name "unconnected-(JP57-Pad3)") (class "Default")
      (node (ref "JP57") (pin "3") (pinfunction "3_3") (pintype "passive"))
    )
    (net (code "415") (name "unconnected-(JP57-Pad4)") (class "Default")
      (node (ref "JP57") (pin "4") (pinfunction "4_4") (pintype "passive"))
    )
    (net (code "416") (name "unconnected-(JP57-Pad5)") (class "Default")
      (node (ref "JP57") (pin "5") (pinfunction "5_5") (pintype "passive"))
    )
    (net (code "417") (name "unconnected-(JP57-Pad6)") (class "Default")
      (node (ref "JP57") (pin "6") (pinfunction "6_6") (pintype "passive"))
    )
    (net (code "418") (name "unconnected-(JP57-Pad7)") (class "Default")
      (node (ref "JP57") (pin "7") (pinfunction "7_7") (pintype "passive"))
    )
    (net (code "419") (name "unconnected-(JP57-Pad8)") (class "Default")
      (node (ref "JP57") (pin "8") (pinfunction "8_8") (pintype "passive"))
    )
    (net (code "420") (name "unconnected-(JP57-Pad9)") (class "Default")
      (node (ref "JP57") (pin "9") (pinfunction "9_9") (pintype "passive"))
    )
    (net (code "421") (name "unconnected-(JP57-Pad10)") (class "Default")
      (node (ref "JP57") (pin "10") (pinfunction "10_10") (pintype "passive"))
    )
    (net (code "422") (name "unconnected-(JP57-Pad11)") (class "Default")
      (node (ref "JP57") (pin "11") (pinfunction "11_11") (pintype "passive"))
    )
    (net (code "423") (name "unconnected-(JP57-Pad12)") (class "Default")
      (node (ref "JP57") (pin "12") (pinfunction "12_12") (pintype "passive"))
    )
    (net (code "424") (name "unconnected-(JP57-Pad13)") (class "Default")
      (node (ref "JP57") (pin "13") (pinfunction "13_13") (pintype "passive"))
    )
    (net (code "425") (name "unconnected-(JP57-Pad14)") (class "Default")
      (node (ref "JP57") (pin "14") (pinfunction "14_14") (pintype "passive"))
    )
    (net (code "426") (name "unconnected-(JP57-Pad15)") (class "Default")
      (node (ref "JP57") (pin "15") (pinfunction "15_15") (pintype "passive"))
    )
    (net (code "427") (name "unconnected-(JP57-Pad16)") (class "Default")
      (node (ref "JP57") (pin "16") (pinfunction "16_16") (pintype "passive"))
    )
  )
)
